# VistelV3.net
KiCad netlist of a schematic drawn in EAGLE
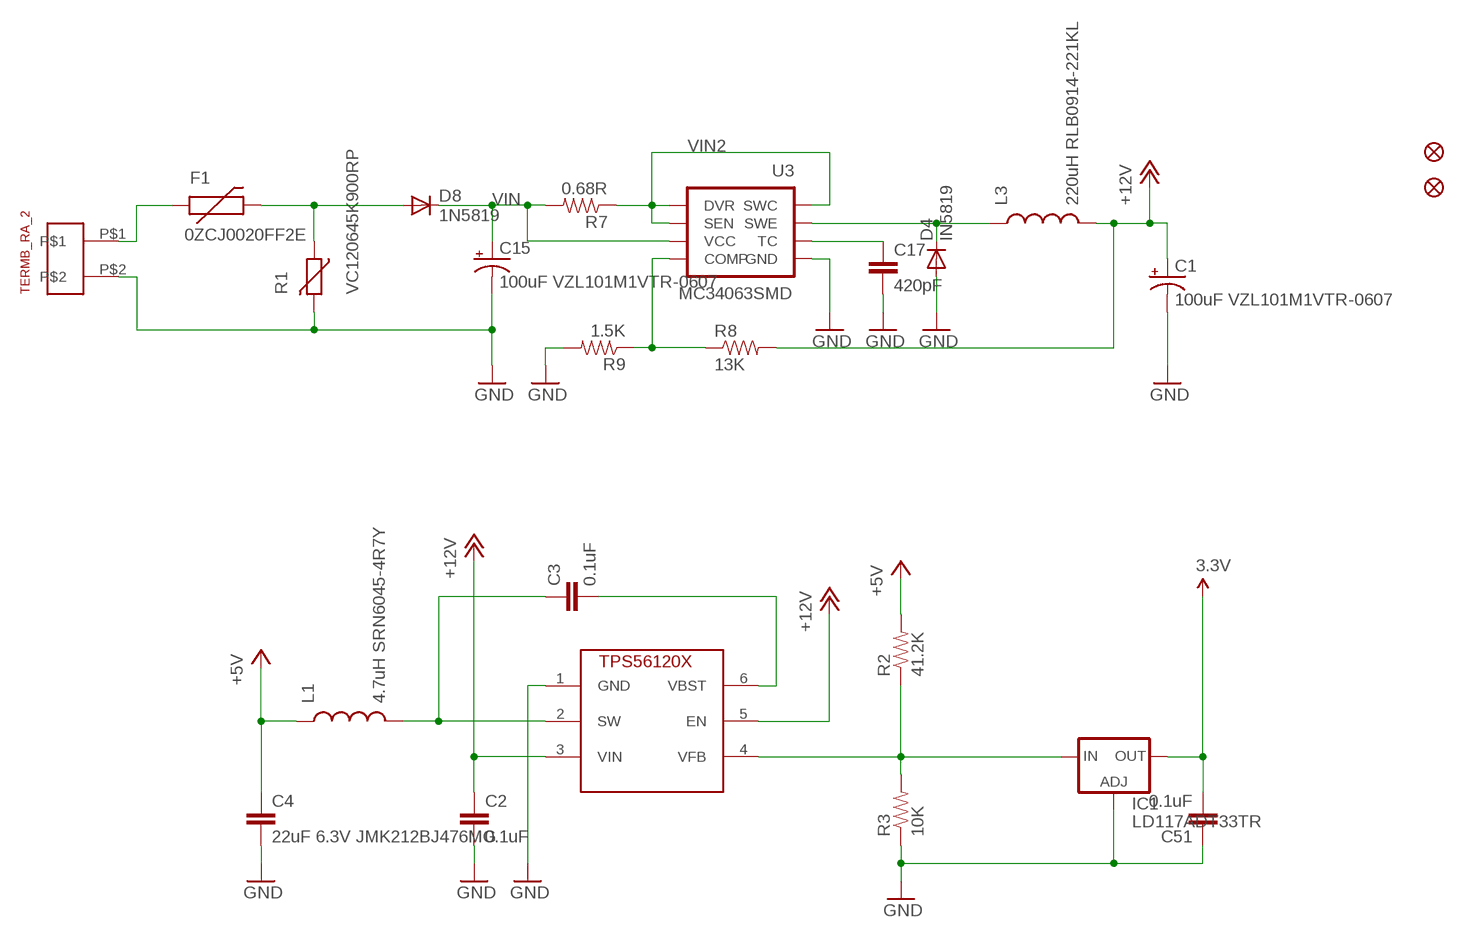
[diagram p0: schematic, sheet 1]
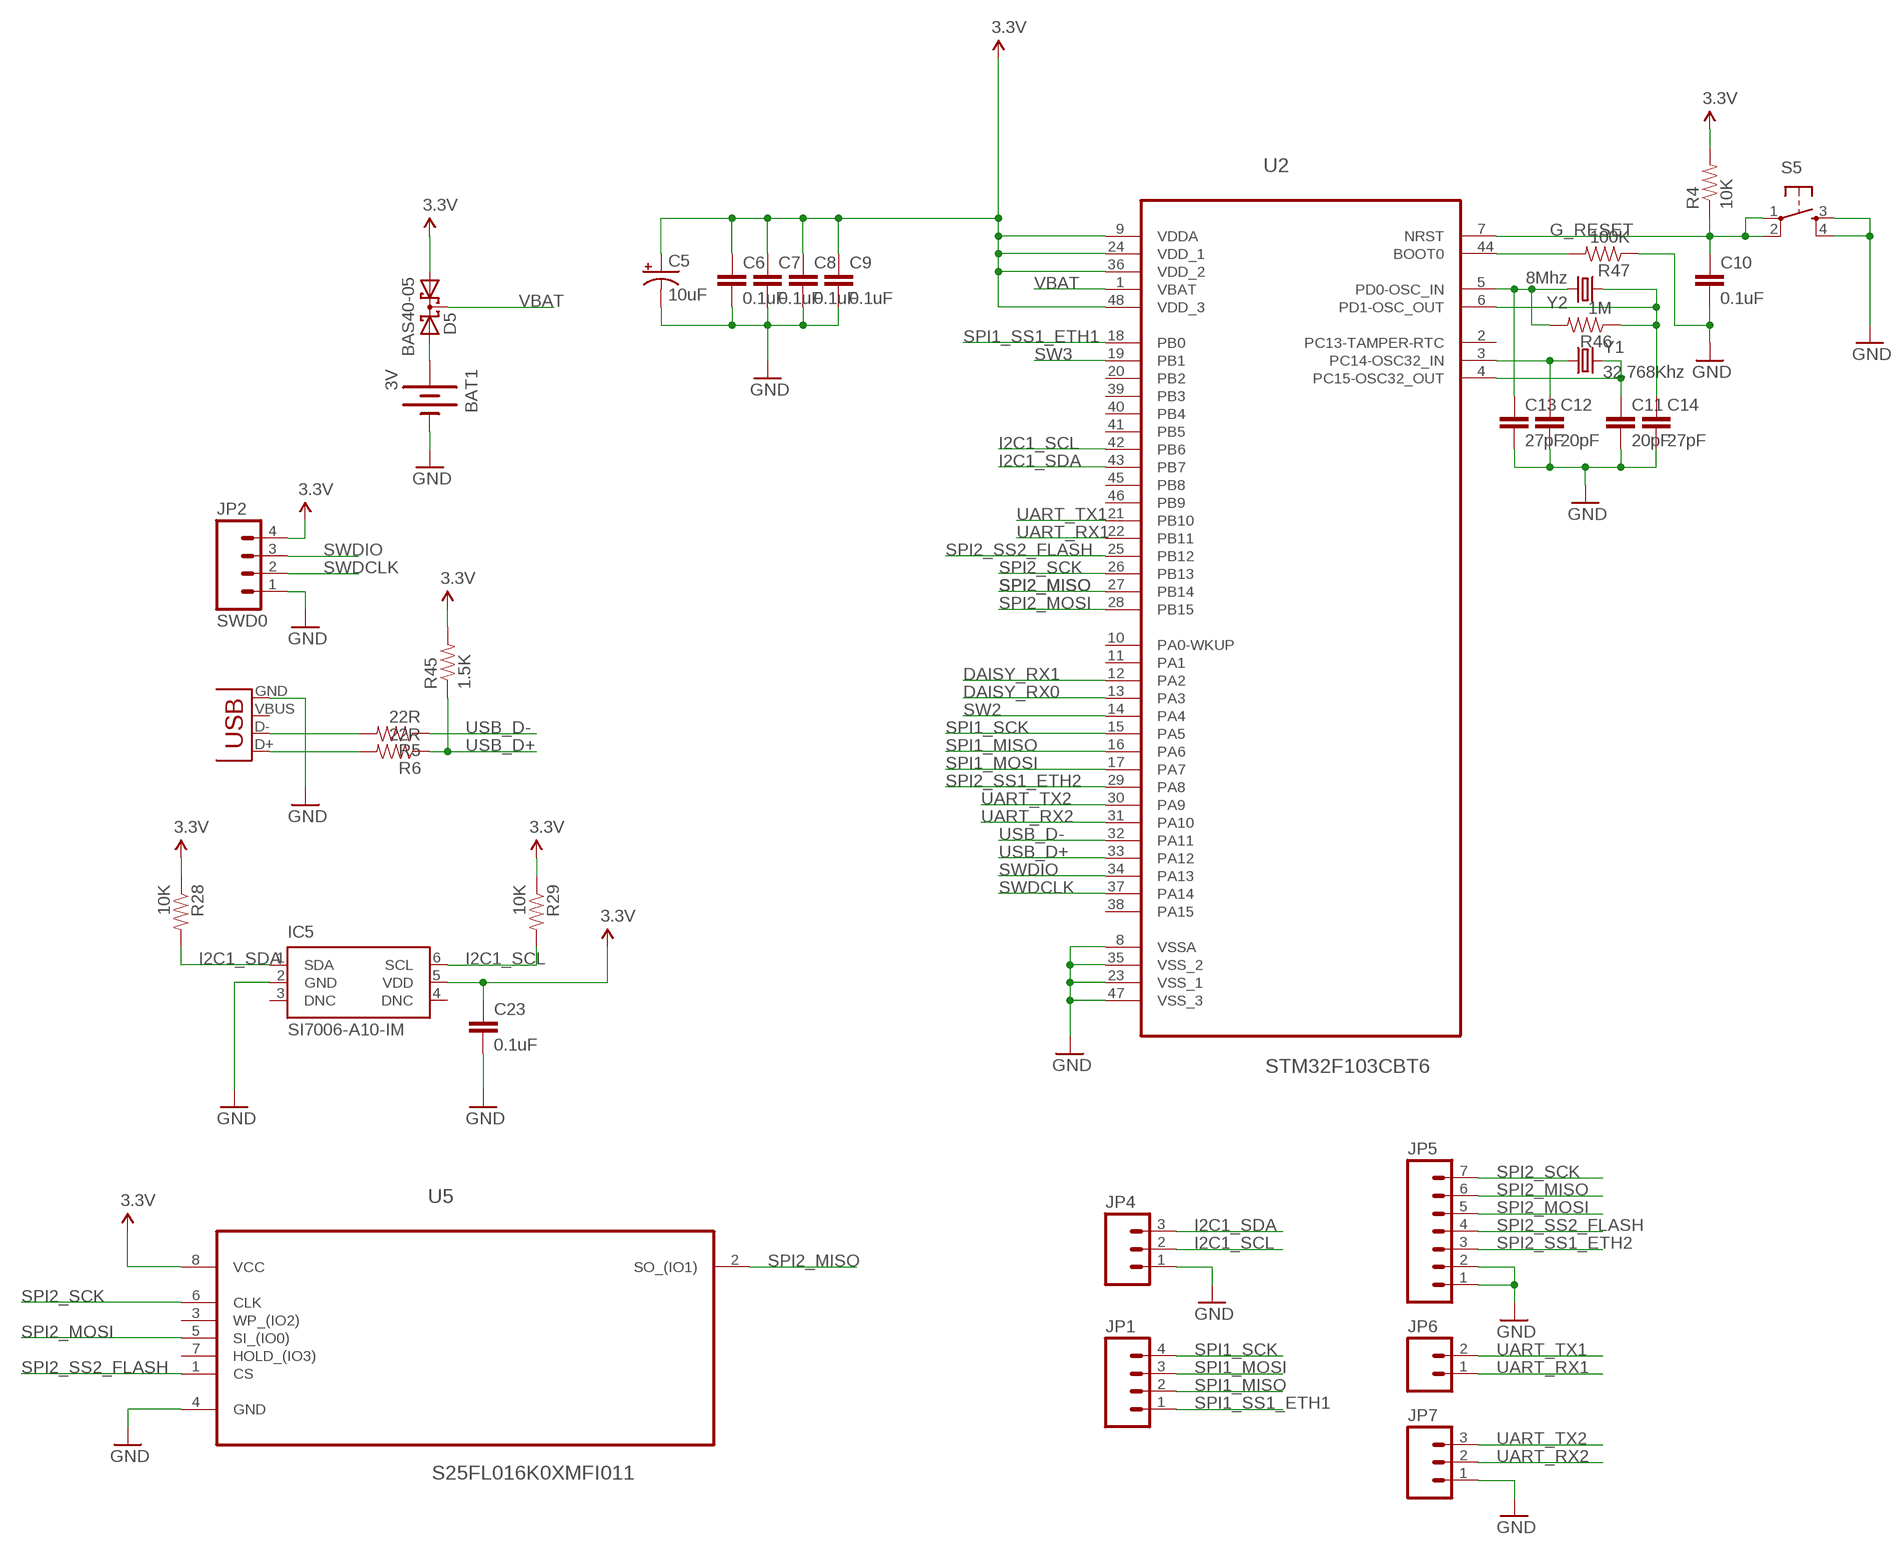
[diagram p1: schematic, sheet 2]
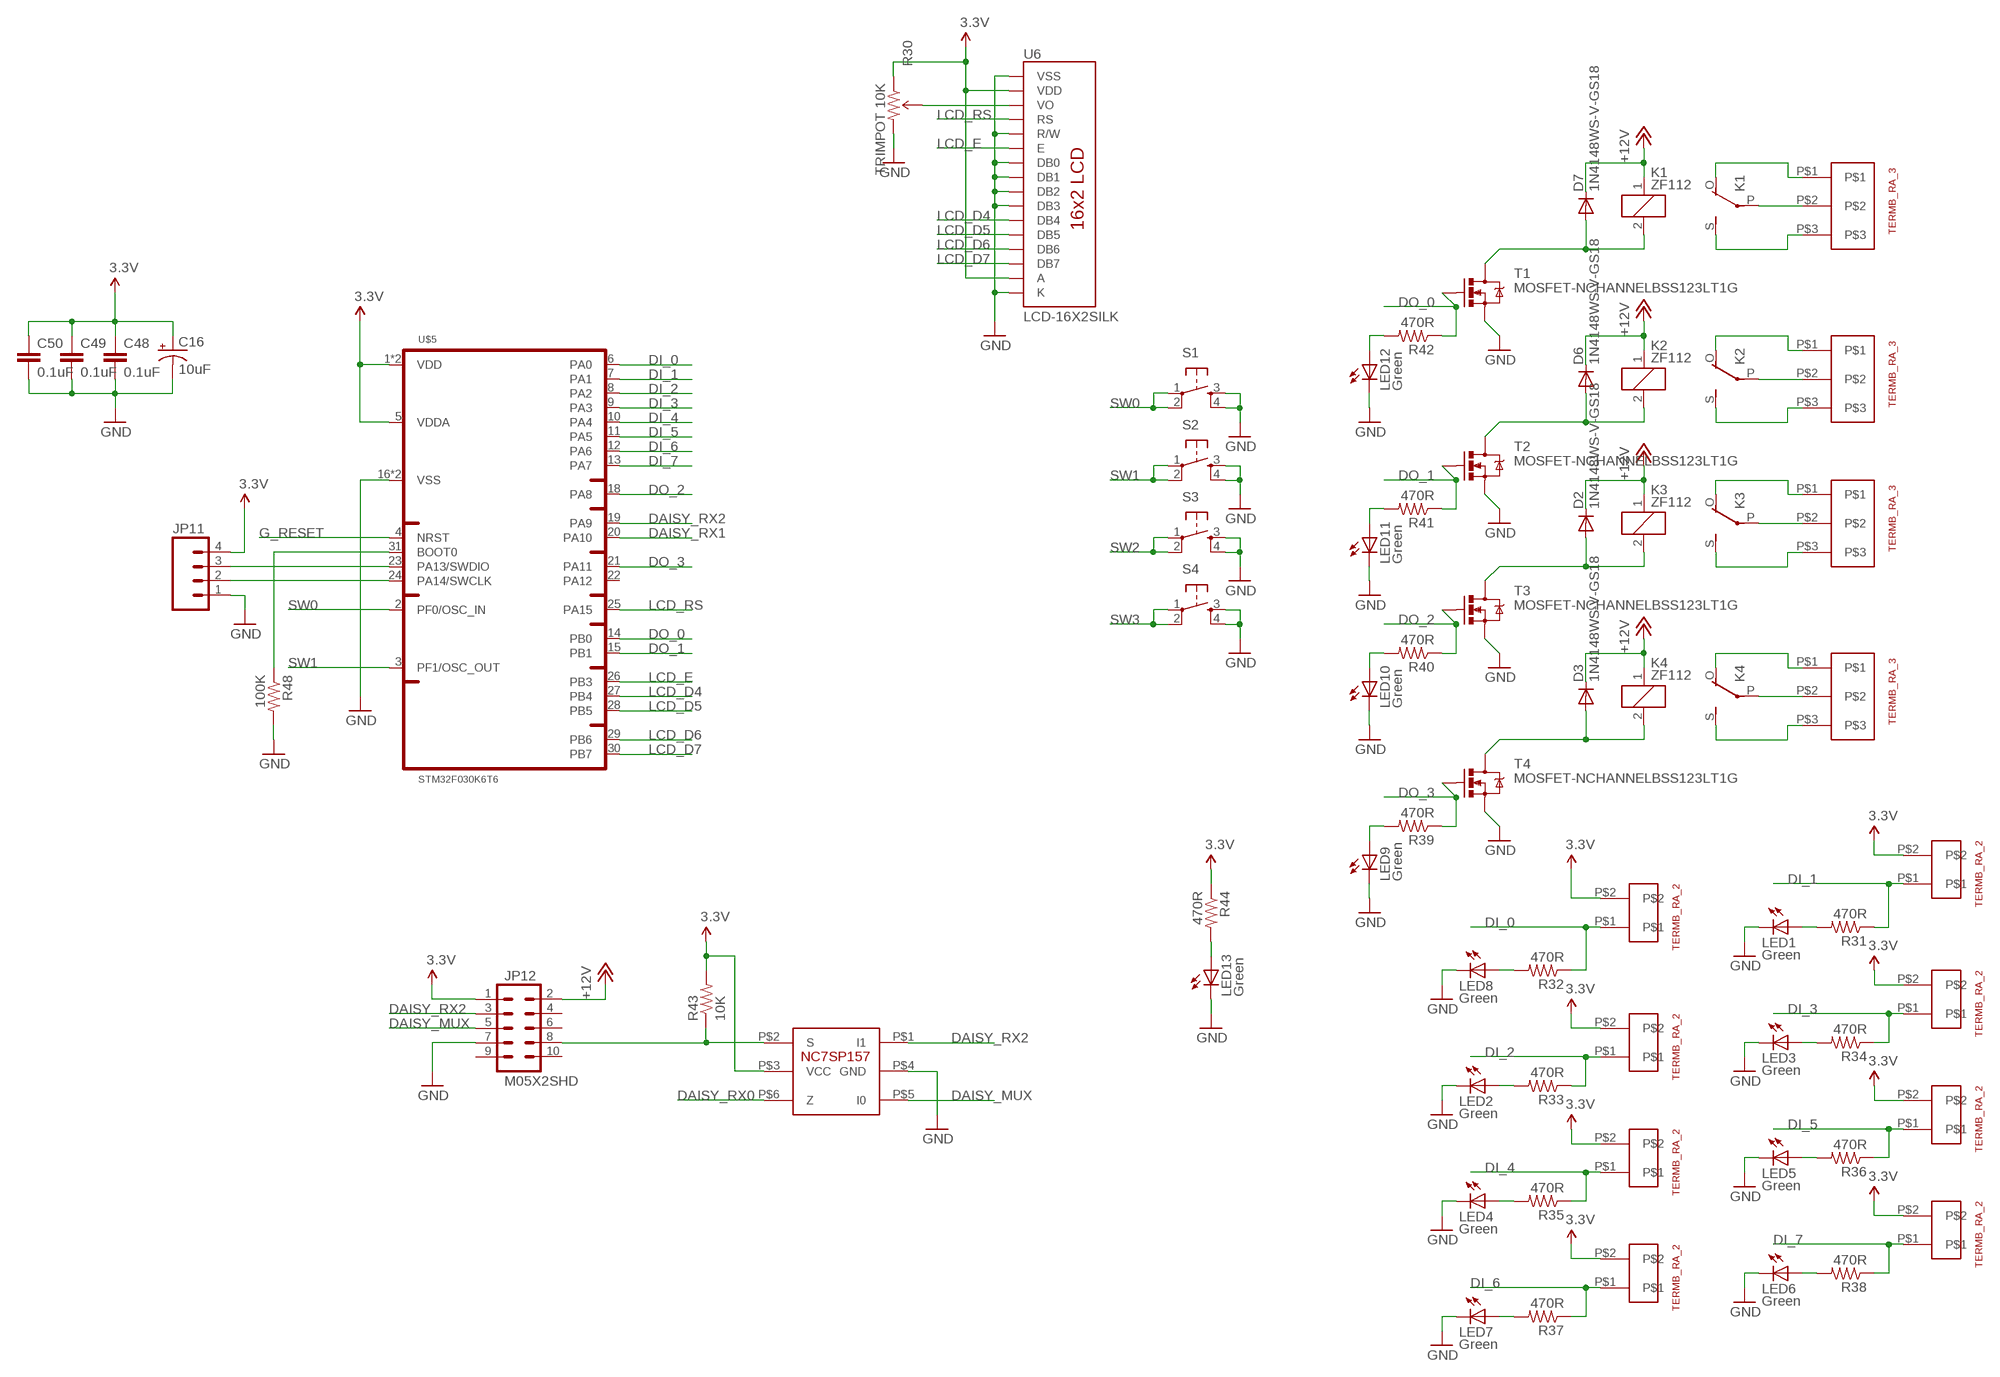
[diagram p2: schematic, sheet 3]
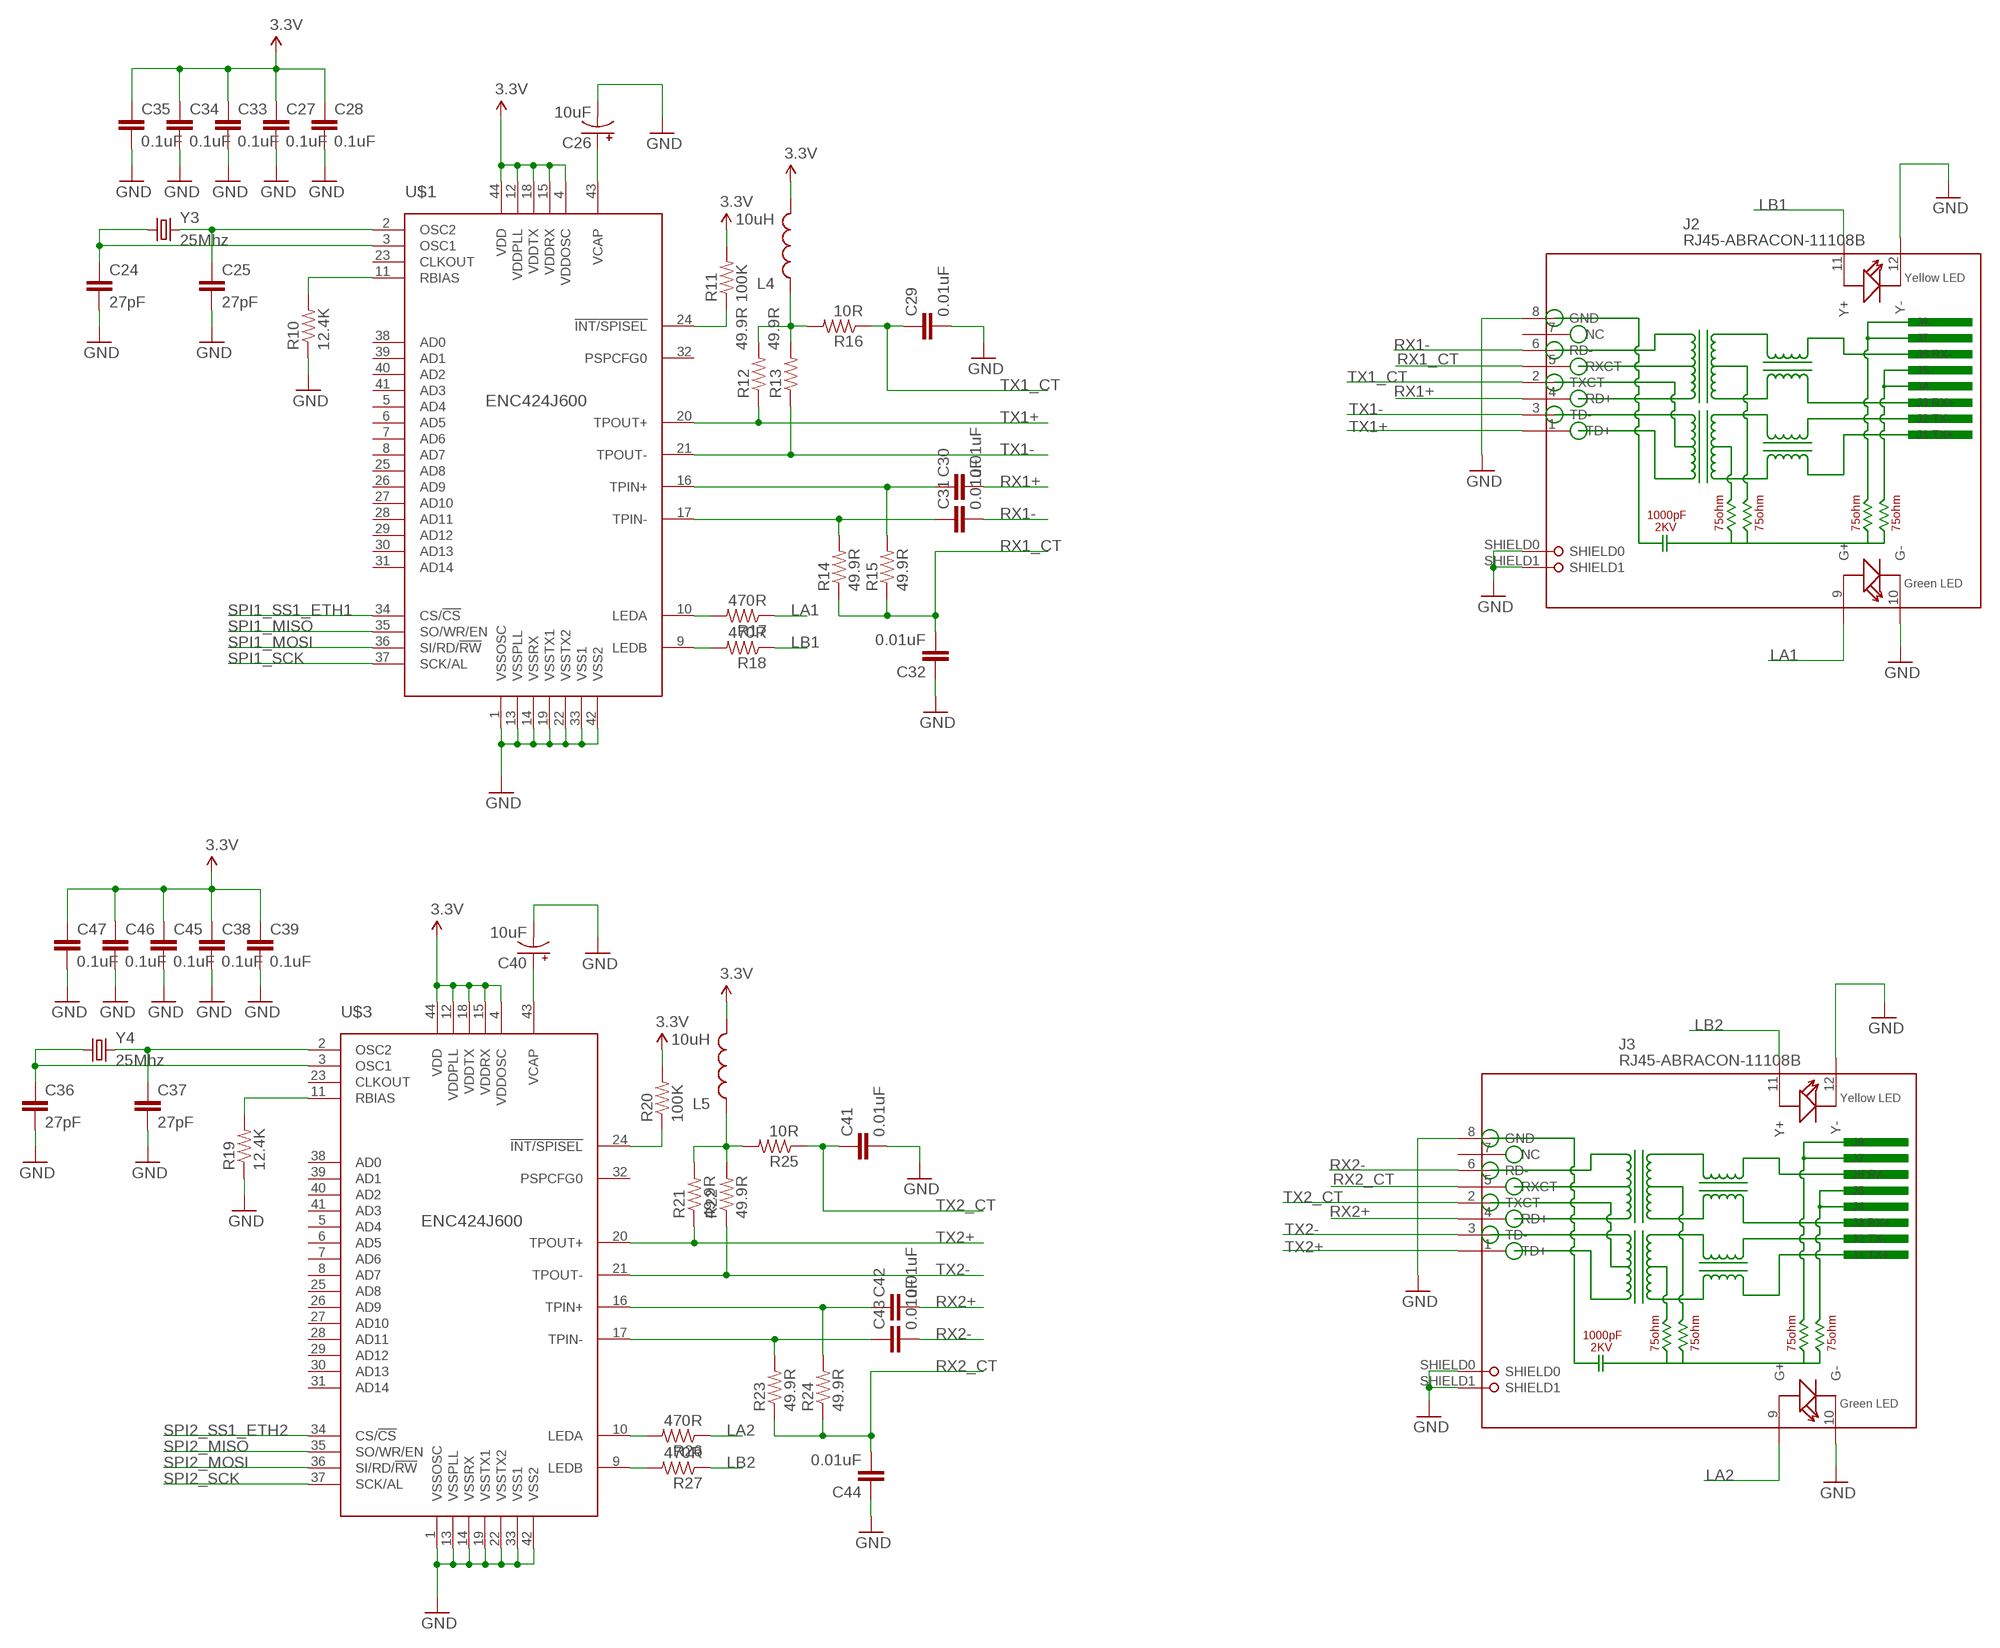
[diagram p3: schematic, sheet 4]
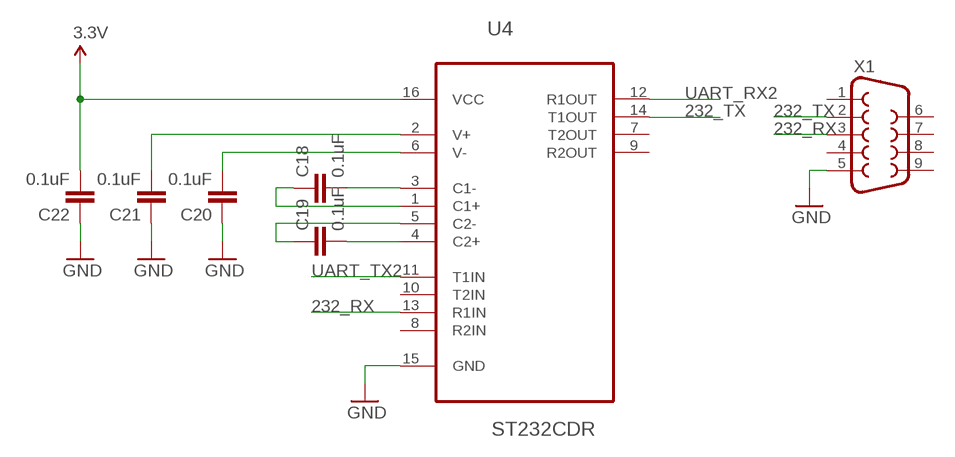
[diagram p4: schematic, sheet 5]

(export (version "E")
  (design (tool "Eeschema 10.0.6"))
  (components
    (comp (ref "C24")
      (value "27pF")
      (footprint "eagle-import:0805")
      (libsource (lib "eagle-import") (part "CAP0805"))
    )
    (comp (ref "C25")
      (value "27pF")
      (footprint "eagle-import:0805")
      (libsource (lib "eagle-import") (part "CAP0805"))
    )
    (comp (ref "C26")
      (value "10uF")
      (footprint "eagle-import:EIA3528-KIT")
      (libsource (lib "eagle-import") (part "CAP_POL3528-KIT"))
    )
    (comp (ref "C27")
      (value "0.1uF")
      (footprint "eagle-import:0805")
      (libsource (lib "eagle-import") (part "CAP0805"))
    )
    (comp (ref "C28")
      (value "0.1uF")
      (footprint "eagle-import:0805")
      (libsource (lib "eagle-import") (part "CAP0805"))
    )
    (comp (ref "C29")
      (value "0.01uF")
      (footprint "eagle-import:0805")
      (libsource (lib "eagle-import") (part "CAP0805"))
    )
    (comp (ref "C30")
      (value "0.01uF")
      (footprint "eagle-import:0805")
      (libsource (lib "eagle-import") (part "CAP0805"))
    )
    (comp (ref "C31")
      (value "0.01uF")
      (footprint "eagle-import:0805")
      (libsource (lib "eagle-import") (part "CAP0805"))
    )
    (comp (ref "C32")
      (value "0.01uF")
      (footprint "eagle-import:0805")
      (libsource (lib "eagle-import") (part "CAP0805"))
    )
    (comp (ref "C33")
      (value "0.1uF")
      (footprint "eagle-import:0805")
      (libsource (lib "eagle-import") (part "CAP0805"))
    )
    (comp (ref "C34")
      (value "0.1uF")
      (footprint "eagle-import:0805")
      (libsource (lib "eagle-import") (part "CAP0805"))
    )
    (comp (ref "C35")
      (value "0.1uF")
      (footprint "eagle-import:0805")
      (libsource (lib "eagle-import") (part "CAP0805"))
    )
    (comp (ref "C36")
      (value "27pF")
      (footprint "eagle-import:0805")
      (libsource (lib "eagle-import") (part "CAP0805"))
    )
    (comp (ref "C37")
      (value "27pF")
      (footprint "eagle-import:0805")
      (libsource (lib "eagle-import") (part "CAP0805"))
    )
    (comp (ref "C38")
      (value "0.1uF")
      (footprint "eagle-import:0805")
      (libsource (lib "eagle-import") (part "CAP0805"))
    )
    (comp (ref "C39")
      (value "0.1uF")
      (footprint "eagle-import:0805")
      (libsource (lib "eagle-import") (part "CAP0805"))
    )
    (comp (ref "C40")
      (value "10uF")
      (footprint "eagle-import:EIA3528-KIT")
      (libsource (lib "eagle-import") (part "CAP_POL3528-KIT"))
    )
    (comp (ref "C41")
      (value "0.01uF")
      (footprint "eagle-import:0805")
      (libsource (lib "eagle-import") (part "CAP0805"))
    )
    (comp (ref "C42")
      (value "0.01uF")
      (footprint "eagle-import:0805")
      (libsource (lib "eagle-import") (part "CAP0805"))
    )
    (comp (ref "C43")
      (value "0.01uF")
      (footprint "eagle-import:0805")
      (libsource (lib "eagle-import") (part "CAP0805"))
    )
    (comp (ref "C44")
      (value "0.01uF")
      (footprint "eagle-import:0805")
      (libsource (lib "eagle-import") (part "CAP0805"))
    )
    (comp (ref "C45")
      (value "0.1uF")
      (footprint "eagle-import:0805")
      (libsource (lib "eagle-import") (part "CAP0805"))
    )
    (comp (ref "C46")
      (value "0.1uF")
      (footprint "eagle-import:0805")
      (libsource (lib "eagle-import") (part "CAP0805"))
    )
    (comp (ref "C47")
      (value "0.1uF")
      (footprint "eagle-import:0805")
      (libsource (lib "eagle-import") (part "CAP0805"))
    )
    (comp (ref "J2")
      (value "RJ45-ABRACON-11108B")
      (footprint "eagle-import:RJ45-ABRACON-111008B")
      (libsource (lib "eagle-import") (part "RJ45-ABRACON-11108B"))
    )
    (comp (ref "J3")
      (value "RJ45-ABRACON-11108B")
      (footprint "eagle-import:RJ45-ABRACON-111008B")
      (libsource (lib "eagle-import") (part "RJ45-ABRACON-11108B"))
    )
    (comp (ref "L4")
      (value "10uH")
      (footprint "eagle-import:0805")
      (libsource (lib "eagle-import") (part "INDUCTOR0805"))
    )
    (comp (ref "L5")
      (value "10uH")
      (footprint "eagle-import:0805")
      (libsource (lib "eagle-import") (part "INDUCTOR0805"))
    )
    (comp (ref "R10")
      (value "12.4K")
      (footprint "eagle-import:0805")
      (libsource (lib "eagle-import") (part "SparkFun-Resistors_RESISTOR0805-RES"))
    )
    (comp (ref "R11")
      (value "100K")
      (footprint "eagle-import:0805")
      (libsource (lib "eagle-import") (part "SparkFun-Resistors_RESISTOR0805-RES"))
    )
    (comp (ref "R12")
      (value "49.9R")
      (footprint "eagle-import:0805")
      (libsource (lib "eagle-import") (part "SparkFun-Resistors_RESISTOR0805-RES"))
    )
    (comp (ref "R13")
      (value "49.9R")
      (footprint "eagle-import:0805")
      (libsource (lib "eagle-import") (part "SparkFun-Resistors_RESISTOR0805-RES"))
    )
    (comp (ref "R14")
      (value "49.9R")
      (footprint "eagle-import:0805")
      (libsource (lib "eagle-import") (part "SparkFun-Resistors_RESISTOR0805-RES"))
    )
    (comp (ref "R15")
      (value "49.9R")
      (footprint "eagle-import:0805")
      (libsource (lib "eagle-import") (part "SparkFun-Resistors_RESISTOR0805-RES"))
    )
    (comp (ref "R16")
      (value "10R")
      (footprint "eagle-import:0805")
      (libsource (lib "eagle-import") (part "SparkFun-Resistors_RESISTOR0805-RES"))
    )
    (comp (ref "R17")
      (value "470R")
      (footprint "eagle-import:0805")
      (libsource (lib "eagle-import") (part "SparkFun-Resistors_RESISTOR0805-RES"))
    )
    (comp (ref "R18")
      (value "470R")
      (footprint "eagle-import:0805")
      (libsource (lib "eagle-import") (part "SparkFun-Resistors_RESISTOR0805-RES"))
    )
    (comp (ref "R19")
      (value "12.4K")
      (footprint "eagle-import:0805")
      (libsource (lib "eagle-import") (part "SparkFun-Resistors_RESISTOR0805-RES"))
    )
    (comp (ref "R20")
      (value "100K")
      (footprint "eagle-import:0805")
      (libsource (lib "eagle-import") (part "SparkFun-Resistors_RESISTOR0805-RES"))
    )
    (comp (ref "R21")
      (value "49.9R")
      (footprint "eagle-import:0805")
      (libsource (lib "eagle-import") (part "SparkFun-Resistors_RESISTOR0805-RES"))
    )
    (comp (ref "R22")
      (value "49.9R")
      (footprint "eagle-import:0805")
      (libsource (lib "eagle-import") (part "SparkFun-Resistors_RESISTOR0805-RES"))
    )
    (comp (ref "R23")
      (value "49.9R")
      (footprint "eagle-import:0805")
      (libsource (lib "eagle-import") (part "SparkFun-Resistors_RESISTOR0805-RES"))
    )
    (comp (ref "R24")
      (value "49.9R")
      (footprint "eagle-import:0805")
      (libsource (lib "eagle-import") (part "SparkFun-Resistors_RESISTOR0805-RES"))
    )
    (comp (ref "R25")
      (value "10R")
      (footprint "eagle-import:0805")
      (libsource (lib "eagle-import") (part "SparkFun-Resistors_RESISTOR0805-RES"))
    )
    (comp (ref "R26")
      (value "470R")
      (footprint "eagle-import:0805")
      (libsource (lib "eagle-import") (part "SparkFun-Resistors_RESISTOR0805-RES"))
    )
    (comp (ref "R27")
      (value "470R")
      (footprint "eagle-import:0805")
      (libsource (lib "eagle-import") (part "SparkFun-Resistors_RESISTOR0805-RES"))
    )
    (comp (ref "U$1")
      (value "ENC424J600")
      (footprint "eagle-import:TQFP-44")
      (libsource (lib "eagle-import") (part "ENC424J600"))
    )
    (comp (ref "U$3")
      (value "ENC424J600")
      (footprint "eagle-import:TQFP-44")
      (libsource (lib "eagle-import") (part "ENC424J600"))
    )
    (comp (ref "Y3")
      (value "25Mhz")
      (footprint "eagle-import:CRYSTAL-SMD-10.5X4.8-2PIN")
      (libsource (lib "eagle-import") (part "CRYSTAL10.5X4.8"))
    )
    (comp (ref "Y4")
      (value "25Mhz")
      (footprint "eagle-import:CRYSTAL-SMD-10.5X4.8-2PIN")
      (libsource (lib "eagle-import") (part "CRYSTAL10.5X4.8"))
    )
    (comp (ref "C16")
      (value "10uF")
      (footprint "eagle-import:EIA3216")
      (libsource (lib "eagle-import") (part "10UF-TANT"))
    )
    (comp (ref "C48")
      (value "0.1uF")
      (footprint "eagle-import:0805")
      (libsource (lib "eagle-import") (part "CAP0805"))
    )
    (comp (ref "C49")
      (value "0.1uF")
      (footprint "eagle-import:0805")
      (libsource (lib "eagle-import") (part "CAP0805"))
    )
    (comp (ref "C50")
      (value "0.1uF")
      (footprint "eagle-import:0805")
      (libsource (lib "eagle-import") (part "CAP0805"))
    )
    (comp (ref "D2")
      (value "1N4148WS-V-GS18")
      (footprint "eagle-import:SMA-DIODE_ALT")
      (libsource (lib "eagle-import") (part "DIODESMA-ALT"))
    )
    (comp (ref "D3")
      (value "1N4148WS-V-GS18")
      (footprint "eagle-import:SMA-DIODE_ALT")
      (libsource (lib "eagle-import") (part "DIODESMA-ALT"))
    )
    (comp (ref "D6")
      (value "1N4148WS-V-GS18")
      (footprint "eagle-import:SMA-DIODE_ALT")
      (libsource (lib "eagle-import") (part "DIODESMA-ALT"))
    )
    (comp (ref "D7")
      (value "1N4148WS-V-GS18")
      (footprint "eagle-import:SMA-DIODE_ALT")
      (libsource (lib "eagle-import") (part "DIODESMA-ALT"))
    )
    (comp (ref "JP11")
      (value "M04PTH")
      (footprint "eagle-import:1X04")
      (libsource (lib "eagle-import") (part "M04PTH"))
    )
    (comp (ref "JP12")
      (value "M05X2SHD")
      (footprint "eagle-import:2X5-SHROUDED")
      (libsource (lib "eagle-import") (part "M05X2SHD"))
    )
    (comp (ref "K1")
      (value "ZF112")
      (footprint "eagle-import:ZF112")
      (libsource (lib "eagle-import") (part "ZF112"))
    )
    (comp (ref "K2")
      (value "ZF112")
      (footprint "eagle-import:ZF112")
      (libsource (lib "eagle-import") (part "ZF112"))
    )
    (comp (ref "K3")
      (value "ZF112")
      (footprint "eagle-import:ZF112")
      (libsource (lib "eagle-import") (part "ZF112"))
    )
    (comp (ref "K4")
      (value "ZF112")
      (footprint "eagle-import:ZF112")
      (libsource (lib "eagle-import") (part "ZF112"))
    )
    (comp (ref "LED1")
      (value "Green")
      (footprint "eagle-import:LED-1206")
      (libsource (lib "eagle-import") (part "LED1206"))
    )
    (comp (ref "LED2")
      (value "Green")
      (footprint "eagle-import:LED-1206")
      (libsource (lib "eagle-import") (part "LED1206"))
    )
    (comp (ref "LED3")
      (value "Green")
      (footprint "eagle-import:LED-1206")
      (libsource (lib "eagle-import") (part "LED1206"))
    )
    (comp (ref "LED4")
      (value "Green")
      (footprint "eagle-import:LED-1206")
      (libsource (lib "eagle-import") (part "LED1206"))
    )
    (comp (ref "LED5")
      (value "Green")
      (footprint "eagle-import:LED-1206")
      (libsource (lib "eagle-import") (part "LED1206"))
    )
    (comp (ref "LED6")
      (value "Green")
      (footprint "eagle-import:LED-1206")
      (libsource (lib "eagle-import") (part "LED1206"))
    )
    (comp (ref "LED7")
      (value "Green")
      (footprint "eagle-import:LED-1206")
      (libsource (lib "eagle-import") (part "LED1206"))
    )
    (comp (ref "LED8")
      (value "Green")
      (footprint "eagle-import:LED-1206")
      (libsource (lib "eagle-import") (part "LED1206"))
    )
    (comp (ref "LED9")
      (value "Green")
      (footprint "eagle-import:LED-1206")
      (libsource (lib "eagle-import") (part "LED1206"))
    )
    (comp (ref "LED10")
      (value "Green")
      (footprint "eagle-import:LED-1206")
      (libsource (lib "eagle-import") (part "LED1206"))
    )
    (comp (ref "LED11")
      (value "Green")
      (footprint "eagle-import:LED-1206")
      (libsource (lib "eagle-import") (part "LED1206"))
    )
    (comp (ref "LED12")
      (value "Green")
      (footprint "eagle-import:LED-1206")
      (libsource (lib "eagle-import") (part "LED1206"))
    )
    (comp (ref "LED13")
      (value "Green")
      (footprint "eagle-import:LED-1206")
      (libsource (lib "eagle-import") (part "LED1206"))
    )
    (comp (ref "R30")
      (value "TRIMPOT 10K")
      (footprint "eagle-import:TRIM_POT_PTH")
      (libsource (lib "eagle-import") (part "TRIMPOTPTH"))
    )
    (comp (ref "R31")
      (value "470R")
      (footprint "eagle-import:0805")
      (libsource (lib "eagle-import") (part "RESISTOR0805-RES"))
    )
    (comp (ref "R32")
      (value "470R")
      (footprint "eagle-import:0805")
      (libsource (lib "eagle-import") (part "RESISTOR0805-RES"))
    )
    (comp (ref "R33")
      (value "470R")
      (footprint "eagle-import:0805")
      (libsource (lib "eagle-import") (part "RESISTOR0805-RES"))
    )
    (comp (ref "R34")
      (value "470R")
      (footprint "eagle-import:0805")
      (libsource (lib "eagle-import") (part "RESISTOR0805-RES"))
    )
    (comp (ref "R35")
      (value "470R")
      (footprint "eagle-import:0805")
      (libsource (lib "eagle-import") (part "RESISTOR0805-RES"))
    )
    (comp (ref "R36")
      (value "470R")
      (footprint "eagle-import:0805")
      (libsource (lib "eagle-import") (part "RESISTOR0805-RES"))
    )
    (comp (ref "R37")
      (value "470R")
      (footprint "eagle-import:0805")
      (libsource (lib "eagle-import") (part "RESISTOR0805-RES"))
    )
    (comp (ref "R38")
      (value "470R")
      (footprint "eagle-import:0805")
      (libsource (lib "eagle-import") (part "RESISTOR0805-RES"))
    )
    (comp (ref "R39")
      (value "470R")
      (footprint "eagle-import:0805")
      (libsource (lib "eagle-import") (part "RESISTOR0805-RES"))
    )
    (comp (ref "R40")
      (value "470R")
      (footprint "eagle-import:0805")
      (libsource (lib "eagle-import") (part "RESISTOR0805-RES"))
    )
    (comp (ref "R41")
      (value "470R")
      (footprint "eagle-import:0805")
      (libsource (lib "eagle-import") (part "RESISTOR0805-RES"))
    )
    (comp (ref "R42")
      (value "470R")
      (footprint "eagle-import:0805")
      (libsource (lib "eagle-import") (part "RESISTOR0805-RES"))
    )
    (comp (ref "R43")
      (value "10K")
      (footprint "eagle-import:0805")
      (libsource (lib "eagle-import") (part "RESISTOR0805-RES"))
    )
    (comp (ref "R44")
      (value "470R")
      (footprint "eagle-import:0805")
      (libsource (lib "eagle-import") (part "RESISTOR0805-RES"))
    )
    (comp (ref "R48")
      (value "100K")
      (footprint "eagle-import:0805")
      (libsource (lib "eagle-import") (part "RESISTOR0805-RES"))
    )
    (comp (ref "S1")
      (value "TAC_SWITCHPTH")
      (footprint "eagle-import:TACTILE-PTH")
      (libsource (lib "eagle-import") (part "TAC_SWITCHPTH"))
    )
    (comp (ref "S2")
      (value "TAC_SWITCHPTH")
      (footprint "eagle-import:TACTILE-PTH")
      (libsource (lib "eagle-import") (part "TAC_SWITCHPTH"))
    )
    (comp (ref "S3")
      (value "TAC_SWITCHPTH")
      (footprint "eagle-import:TACTILE-PTH")
      (libsource (lib "eagle-import") (part "TAC_SWITCHPTH"))
    )
    (comp (ref "S4")
      (value "TAC_SWITCHPTH")
      (footprint "eagle-import:TACTILE-PTH")
      (libsource (lib "eagle-import") (part "TAC_SWITCHPTH"))
    )
    (comp (ref "T1")
      (value "MOSFET-NCHANNELBSS123LT1G")
      (footprint "eagle-import:SOT23")
      (libsource (lib "eagle-import") (part "MOSFET-NCHANNELBSS123LT1G"))
    )
    (comp (ref "T2")
      (value "MOSFET-NCHANNELBSS123LT1G")
      (footprint "eagle-import:SOT23")
      (libsource (lib "eagle-import") (part "MOSFET-NCHANNELBSS123LT1G"))
    )
    (comp (ref "T3")
      (value "MOSFET-NCHANNELBSS123LT1G")
      (footprint "eagle-import:SOT23")
      (libsource (lib "eagle-import") (part "MOSFET-NCHANNELBSS123LT1G"))
    )
    (comp (ref "T4")
      (value "MOSFET-NCHANNELBSS123LT1G")
      (footprint "eagle-import:SOT23")
      (libsource (lib "eagle-import") (part "MOSFET-NCHANNELBSS123LT1G"))
    )
    (comp (ref "U$4")
      (value "NC7SP157")
      (footprint "eagle-import:SC70-6")
      (libsource (lib "eagle-import") (part "NC7SP157"))
    )
    (comp (ref "U$5")
      (value "STM32F030K6T6")
      (footprint "eagle-import:LQFP32-7X7")
      (libsource (lib "eagle-import") (part "STM32F030K6T6"))
    )
    (comp (ref "U$6")
      (value "1X02_TERMB_RA")
      (footprint "eagle-import:1X02_TERMB_RA")
      (libsource (lib "eagle-import") (part "1X02_TERMB_RA"))
    )
    (comp (ref "U$7")
      (value "1X02_TERMB_RA")
      (footprint "eagle-import:1X02_TERMB_RA")
      (libsource (lib "eagle-import") (part "1X02_TERMB_RA"))
    )
    (comp (ref "U$8")
      (value "1X02_TERMB_RA")
      (footprint "eagle-import:1X02_TERMB_RA")
      (libsource (lib "eagle-import") (part "1X02_TERMB_RA"))
    )
    (comp (ref "U$9")
      (value "1X02_TERMB_RA")
      (footprint "eagle-import:1X02_TERMB_RA")
      (libsource (lib "eagle-import") (part "1X02_TERMB_RA"))
    )
    (comp (ref "U$10")
      (value "1X02_TERMB_RA")
      (footprint "eagle-import:1X02_TERMB_RA")
      (libsource (lib "eagle-import") (part "1X02_TERMB_RA"))
    )
    (comp (ref "U$11")
      (value "1X02_TERMB_RA")
      (footprint "eagle-import:1X02_TERMB_RA")
      (libsource (lib "eagle-import") (part "1X02_TERMB_RA"))
    )
    (comp (ref "U$12")
      (value "1X02_TERMB_RA")
      (footprint "eagle-import:1X02_TERMB_RA")
      (libsource (lib "eagle-import") (part "1X02_TERMB_RA"))
    )
    (comp (ref "U$13")
      (value "1X02_TERMB_RA")
      (footprint "eagle-import:1X02_TERMB_RA")
      (libsource (lib "eagle-import") (part "1X02_TERMB_RA"))
    )
    (comp (ref "U$14")
      (value "1X03_TERMB_RA")
      (footprint "eagle-import:1X03_TERMB_RA")
      (libsource (lib "eagle-import") (part "1X03_TERMB_RA"))
    )
    (comp (ref "U$15")
      (value "1X03_TERMB_RA")
      (footprint "eagle-import:1X03_TERMB_RA")
      (libsource (lib "eagle-import") (part "1X03_TERMB_RA"))
    )
    (comp (ref "U$16")
      (value "1X03_TERMB_RA")
      (footprint "eagle-import:1X03_TERMB_RA")
      (libsource (lib "eagle-import") (part "1X03_TERMB_RA"))
    )
    (comp (ref "U$17")
      (value "1X03_TERMB_RA")
      (footprint "eagle-import:1X03_TERMB_RA")
      (libsource (lib "eagle-import") (part "1X03_TERMB_RA"))
    )
    (comp (ref "U6")
      (value "LCD-16X2SILK")
      (footprint "eagle-import:LCD-16X2")
      (libsource (lib "eagle-import") (part "LCD-16X2SILK"))
    )
    (comp (ref "C18")
      (value "0.1uF")
      (footprint "eagle-import:0805")
      (libsource (lib "eagle-import") (part "SparkFun-Passives_CAP0805"))
    )
    (comp (ref "C19")
      (value "0.1uF")
      (footprint "eagle-import:0805")
      (libsource (lib "eagle-import") (part "SparkFun-Passives_CAP0805"))
    )
    (comp (ref "C20")
      (value "0.1uF")
      (footprint "eagle-import:0805")
      (libsource (lib "eagle-import") (part "SparkFun-Passives_CAP0805"))
    )
    (comp (ref "C21")
      (value "0.1uF")
      (footprint "eagle-import:0805")
      (libsource (lib "eagle-import") (part "SparkFun-Passives_CAP0805"))
    )
    (comp (ref "C22")
      (value "0.1uF")
      (footprint "eagle-import:0805")
      (libsource (lib "eagle-import") (part "SparkFun-Passives_CAP0805"))
    )
    (comp (ref "U4")
      (value "ST232CDR")
      (footprint "eagle-import:SOIC127P600X175-16N")
      (libsource (lib "eagle-import") (part "ST232CDR"))
    )
    (comp (ref "X1")
      (value "DB9FEMALE")
      (footprint "eagle-import:DB9")
      (libsource (lib "eagle-import") (part "DB9FEMALE"))
    )
    (comp (ref "BAT1")
      (value "3V")
      (footprint "eagle-import:BATTCOM_20MM_PTH")
      (libsource (lib "eagle-import") (part "BATTERY20PTH"))
    )
    (comp (ref "C5")
      (value "10uF")
      (footprint "eagle-import:EIA3216")
      (libsource (lib "eagle-import") (part "10UF-TANT"))
    )
    (comp (ref "C6")
      (value "0.1uF")
      (footprint "eagle-import:0805")
      (libsource (lib "eagle-import") (part "CAP0805"))
    )
    (comp (ref "C7")
      (value "0.1uF")
      (footprint "eagle-import:0805")
      (libsource (lib "eagle-import") (part "CAP0805"))
    )
    (comp (ref "C8")
      (value "0.1uF")
      (footprint "eagle-import:0805")
      (libsource (lib "eagle-import") (part "CAP0805"))
    )
    (comp (ref "C9")
      (value "0.1uF")
      (footprint "eagle-import:0805")
      (libsource (lib "eagle-import") (part "CAP0805"))
    )
    (comp (ref "C10")
      (value "0.1uF")
      (footprint "eagle-import:0805")
      (libsource (lib "eagle-import") (part "CAP0805"))
    )
    (comp (ref "C11")
      (value "20pF")
      (footprint "eagle-import:0805")
      (libsource (lib "eagle-import") (part "CAP0805"))
    )
    (comp (ref "C12")
      (value "20pF")
      (footprint "eagle-import:0805")
      (libsource (lib "eagle-import") (part "CAP0805"))
    )
    (comp (ref "C13")
      (value "27pF")
      (footprint "eagle-import:0805")
      (libsource (lib "eagle-import") (part "CAP0805"))
    )
    (comp (ref "C14")
      (value "27pF")
      (footprint "eagle-import:0805")
      (libsource (lib "eagle-import") (part "CAP0805"))
    )
    (comp (ref "C23")
      (value "0.1uF")
      (footprint "eagle-import:0805")
      (libsource (lib "eagle-import") (part "CAP0805"))
    )
    (comp (ref "D5")
      (value "BAS40-05")
      (footprint "eagle-import:SOT23")
      (libsource (lib "eagle-import") (part "BAS40-05"))
    )
    (comp (ref "IC5")
      (value "SI7006-A10-IM")
      (footprint "eagle-import:DFN6-3X3")
      (fields (field (name "MF") "Silicon Labs") (field (name "MPN") "Si7006-A10-IM"))
      (libsource (lib "eagle-import") (part "SI7006-A10-IM"))
    )
    (comp (ref "JP1")
      (value "M04PTH")
      (footprint "eagle-import:1X04")
      (libsource (lib "eagle-import") (part "M04PTH"))
    )
    (comp (ref "JP2")
      (value "SWD0")
      (footprint "eagle-import:1X04")
      (libsource (lib "eagle-import") (part "M04PTH"))
    )
    (comp (ref "JP3")
      (value "USB-B")
      (footprint "eagle-import:USB-B-PTH")
      (libsource (lib "eagle-import") (part "USBPTH"))
    )
    (comp (ref "JP4")
      (value "M03PTH")
      (footprint "eagle-import:1X03")
      (libsource (lib "eagle-import") (part "M03PTH"))
    )
    (comp (ref "JP5")
      (value "M07")
      (footprint "eagle-import:1X07")
      (libsource (lib "eagle-import") (part "M07"))
    )
    (comp (ref "JP6")
      (value "M02PTH")
      (footprint "eagle-import:1X02")
      (libsource (lib "eagle-import") (part "M02PTH"))
    )
    (comp (ref "JP7")
      (value "M03PTH")
      (footprint "eagle-import:1X03")
      (libsource (lib "eagle-import") (part "M03PTH"))
    )
    (comp (ref "R4")
      (value "10K")
      (footprint "eagle-import:0805")
      (libsource (lib "eagle-import") (part "SparkFun-Resistors_RESISTOR0805-RES"))
    )
    (comp (ref "R5")
      (value "22R")
      (footprint "eagle-import:0805")
      (libsource (lib "eagle-import") (part "SparkFun-Resistors_RESISTOR0805-RES"))
    )
    (comp (ref "R6")
      (value "22R")
      (footprint "eagle-import:0805")
      (libsource (lib "eagle-import") (part "SparkFun-Resistors_RESISTOR0805-RES"))
    )
    (comp (ref "R28")
      (value "10K")
      (footprint "eagle-import:0805")
      (libsource (lib "eagle-import") (part "SparkFun-Resistors_RESISTOR0805-RES"))
    )
    (comp (ref "R29")
      (value "10K")
      (footprint "eagle-import:0805")
      (libsource (lib "eagle-import") (part "SparkFun-Resistors_RESISTOR0805-RES"))
    )
    (comp (ref "R45")
      (value "1.5K")
      (footprint "eagle-import:0805")
      (libsource (lib "eagle-import") (part "SparkFun-Resistors_RESISTOR0805-RES"))
    )
    (comp (ref "R46")
      (value "1M")
      (footprint "eagle-import:0805")
      (libsource (lib "eagle-import") (part "SparkFun-Resistors_RESISTOR0805-RES"))
    )
    (comp (ref "R47")
      (value "100K")
      (footprint "eagle-import:0805")
      (libsource (lib "eagle-import") (part "SparkFun-Resistors_RESISTOR0805-RES"))
    )
    (comp (ref "S5")
      (value "TAC_SWITCHPTH")
      (footprint "eagle-import:TACTILE-PTH")
      (libsource (lib "eagle-import") (part "TAC_SWITCHPTH"))
    )
    (comp (ref "U2")
      (value "STM32F103CBT6")
      (footprint "eagle-import:QFP50P900X900X160-48N")
      (libsource (lib "eagle-import") (part "STM32F103CBT6"))
    )
    (comp (ref "U5")
      (value "S25FL016K0XMFI011")
      (footprint "eagle-import:SOIC127P800X215-8N")
      (libsource (lib "eagle-import") (part "S25FL016K0XMFI011"))
    )
    (comp (ref "Y1")
      (value "32.768Khz")
      (footprint "eagle-import:MC-306")
      (fields (field (name "MPN") "MC-306 60.0KHZ  100PPM ,12.5PF"))
      (libsource (lib "eagle-import") (part "MC-306"))
    )
    (comp (ref "Y2")
      (value "8Mhz")
      (footprint "eagle-import:HC49US")
      (libsource (lib "eagle-import") (part "CRYSTALHC49US"))
    )
    (comp (ref "C1")
      (value "100uF VZL101M1VTR-0607")
      (footprint "eagle-import:PANASONIC_D")
      (libsource (lib "eagle-import") (part "CAP_POLD"))
    )
    (comp (ref "C2")
      (value "0.1uF")
      (footprint "eagle-import:0805")
      (libsource (lib "eagle-import") (part "SparkFun-Passives_CAP0805"))
    )
    (comp (ref "C3")
      (value "0.1uF")
      (footprint "eagle-import:0805")
      (libsource (lib "eagle-import") (part "SparkFun-Passives_CAP0805"))
    )
    (comp (ref "C4")
      (value "22uF 6.3V JMK212BJ476MG")
      (footprint "eagle-import:0805")
      (libsource (lib "eagle-import") (part "SparkFun-Passives_CAP0805"))
    )
    (comp (ref "C15")
      (value "100uF VZL101M1VTR-0607")
      (footprint "eagle-import:PANASONIC_D")
      (libsource (lib "eagle-import") (part "CAP_POLD"))
    )
    (comp (ref "C17")
      (value "420pF")
      (footprint "eagle-import:0805")
      (libsource (lib "eagle-import") (part "SparkFun-Passives_CAP0805"))
    )
    (comp (ref "C51")
      (value "0.1uF")
      (footprint "eagle-import:0805")
      (libsource (lib "eagle-import") (part "SparkFun-Passives_CAP0805"))
    )
    (comp (ref "D4")
      (value "IN5819")
      (footprint "eagle-import:SMA-DIODE")
      (libsource (lib "eagle-import") (part "DIODESMA"))
    )
    (comp (ref "D8")
      (value "1N5819")
      (footprint "eagle-import:SMB-DIODE")
      (libsource (lib "eagle-import") (part "DIODESMB"))
    )
    (comp (ref "F1")
      (value "0ZCJ0020FF2E")
      (footprint "eagle-import:PTC-1206")
      (libsource (lib "eagle-import") (part "PTCSMD"))
    )
    (comp (ref "FID1")
      (value "FIDUCIAL1.5X3")
      (footprint "eagle-import:FIDUCIAL-1.5X3")
      (libsource (lib "eagle-import") (part "FIDUCIAL1.5X3"))
    )
    (comp (ref "FID2")
      (value "FIDUCIAL1.5X3")
      (footprint "eagle-import:FIDUCIAL-1.5X3")
      (libsource (lib "eagle-import") (part "FIDUCIAL1.5X3"))
    )
    (comp (ref "IC1")
      (value "LD117ADT33TR")
      (footprint "eagle-import:DPACK")
      (libsource (lib "eagle-import") (part "LD117A?DT33TR"))
    )
    (comp (ref "L1")
      (value "4.7uH SRN6045-4R7Y")
      (footprint "eagle-import:0805")
      (libsource (lib "eagle-import") (part "INDUCTOR0805"))
    )
    (comp (ref "L3")
      (value "220uH RLB0914-221KL")
      (footprint "eagle-import:RLB914-IND")
      (libsource (lib "eagle-import") (part "INDUCTORRADIAL5MM"))
    )
    (comp (ref "R1")
      (value "VC120645K900RP")
      (footprint "eagle-import:CT_CN1206")
      (libsource (lib "eagle-import") (part "VARISTORCN1206"))
    )
    (comp (ref "R2")
      (value "41.2K")
      (footprint "eagle-import:0805")
      (libsource (lib "eagle-import") (part "RESISTOR0805-RES"))
    )
    (comp (ref "R3")
      (value "10K")
      (footprint "eagle-import:0805")
      (libsource (lib "eagle-import") (part "RESISTOR0805-RES"))
    )
    (comp (ref "R7")
      (value "0.68R")
      (footprint "eagle-import:0805")
      (libsource (lib "eagle-import") (part "RESISTOR0805-RES"))
    )
    (comp (ref "R8")
      (value "13K")
      (footprint "eagle-import:0805")
      (libsource (lib "eagle-import") (part "RESISTOR0805-RES"))
    )
    (comp (ref "R9")
      (value "1.5K")
      (footprint "eagle-import:0805")
      (libsource (lib "eagle-import") (part "RESISTOR0805-RES"))
    )
    (comp (ref "U$2")
      (value "1X02_TERMB_RA")
      (footprint "eagle-import:1X02_TERMB_RA")
      (libsource (lib "eagle-import") (part "1X02_TERMB_RA"))
    )
    (comp (ref "U$18")
      (value "TPS56120X")
      (footprint "eagle-import:TSOT23-6_DDC")
      (libsource (lib "eagle-import") (part "TPS56120X"))
    )
    (comp (ref "U3")
      (value "MC34063SMD")
      (footprint "eagle-import:SO08")
      (libsource (lib "eagle-import") (part "MC34063SMD"))
    )
  )
  (nets
    (net (code "1") (name "+5V") (class "Default")
      (node (ref "C4") (pin "1") (pinfunction "1_1") (pintype "passive"))
      (node (ref "L1") (pin "1") (pinfunction "1_1") (pintype "passive"))
      (node (ref "R2") (pin "2") (pinfunction "2_2") (pintype "passive"))
    )
    (net (code "2") (name "+12V") (class "Default")
      (node (ref "C1") (pin "+") (pinfunction "+_+") (pintype "passive"))
      (node (ref "C2") (pin "1") (pinfunction "1_1") (pintype "passive"))
      (node (ref "D2") (pin "C") (pinfunction "C_C") (pintype "passive"))
      (node (ref "D3") (pin "C") (pinfunction "C_C") (pintype "passive"))
      (node (ref "D6") (pin "C") (pinfunction "C_C") (pintype "passive"))
      (node (ref "D7") (pin "C") (pinfunction "C_C") (pintype "passive"))
      (node (ref "JP12") (pin "2") (pinfunction "2_2") (pintype "passive"))
      (node (ref "K1") (pin "1") (pinfunction "1_1") (pintype "passive"))
      (node (ref "K2") (pin "1") (pinfunction "1_1") (pintype "passive"))
      (node (ref "K3") (pin "1") (pinfunction "1_1") (pintype "passive"))
      (node (ref "K4") (pin "1") (pinfunction "1_1") (pintype "passive"))
      (node (ref "L3") (pin "P$2") (pinfunction "2_P$2") (pintype "passive"))
      (node (ref "R8") (pin "2") (pinfunction "2_2") (pintype "passive"))
      (node (ref "U$18") (pin "3") (pinfunction "VIN_3") (pintype "bidirectional"))
      (node (ref "U$18") (pin "5") (pinfunction "EN_5") (pintype "bidirectional"))
    )
    (net (code "3") (name "3.3V") (class "Default")
      (node (ref "C16") (pin "A") (pinfunction "+_A") (pintype "passive"))
      (node (ref "C22") (pin "2") (pinfunction "2_2") (pintype "passive"))
      (node (ref "C23") (pin "1") (pinfunction "1_1") (pintype "passive"))
      (node (ref "C27") (pin "1") (pinfunction "1_1") (pintype "passive"))
      (node (ref "C28") (pin "1") (pinfunction "1_1") (pintype "passive"))
      (node (ref "C33") (pin "1") (pinfunction "1_1") (pintype "passive"))
      (node (ref "C34") (pin "1") (pinfunction "1_1") (pintype "passive"))
      (node (ref "C35") (pin "1") (pinfunction "1_1") (pintype "passive"))
      (node (ref "C38") (pin "1") (pinfunction "1_1") (pintype "passive"))
      (node (ref "C39") (pin "1") (pinfunction "1_1") (pintype "passive"))
      (node (ref "C45") (pin "1") (pinfunction "1_1") (pintype "passive"))
      (node (ref "C46") (pin "1") (pinfunction "1_1") (pintype "passive"))
      (node (ref "C47") (pin "1") (pinfunction "1_1") (pintype "passive"))
      (node (ref "C48") (pin "1") (pinfunction "1_1") (pintype "passive"))
      (node (ref "C49") (pin "1") (pinfunction "1_1") (pintype "passive"))
      (node (ref "C5") (pin "A") (pinfunction "+_A") (pintype "passive"))
      (node (ref "C50") (pin "1") (pinfunction "1_1") (pintype "passive"))
      (node (ref "C51") (pin "2") (pinfunction "2_2") (pintype "passive"))
      (node (ref "C6") (pin "1") (pinfunction "1_1") (pintype "passive"))
      (node (ref "C7") (pin "1") (pinfunction "1_1") (pintype "passive"))
      (node (ref "C8") (pin "1") (pinfunction "1_1") (pintype "passive"))
      (node (ref "C9") (pin "1") (pinfunction "1_1") (pintype "passive"))
      (node (ref "D5") (pin "1") (pinfunction "A1_1") (pintype "passive"))
      (node (ref "IC1") (pin "4") (pinfunction "OUT_4") (pintype "passive"))
      (node (ref "IC5") (pin "5") (pinfunction "VDD_5") (pintype "power_in"))
      (node (ref "JP11") (pin "4") (pinfunction "4_4") (pintype "passive"))
      (node (ref "JP12") (pin "1") (pinfunction "1_1") (pintype "passive"))
      (node (ref "JP2") (pin "4") (pinfunction "4_4") (pintype "passive"))
      (node (ref "L4") (pin "2") (pinfunction "2_2") (pintype "passive"))
      (node (ref "L5") (pin "2") (pinfunction "2_2") (pintype "passive"))
      (node (ref "R11") (pin "2") (pinfunction "2_2") (pintype "passive"))
      (node (ref "R20") (pin "2") (pinfunction "2_2") (pintype "passive"))
      (node (ref "R28") (pin "1") (pinfunction "1_1") (pintype "passive"))
      (node (ref "R29") (pin "1") (pinfunction "1_1") (pintype "passive"))
      (node (ref "R30") (pin "1") (pinfunction "CCW_1") (pintype "passive"))
      (node (ref "R4") (pin "2") (pinfunction "2_2") (pintype "passive"))
      (node (ref "R43") (pin "2") (pinfunction "2_2") (pintype "passive"))
      (node (ref "R44") (pin "1") (pinfunction "1_1") (pintype "passive"))
      (node (ref "R45") (pin "2") (pinfunction "2_2") (pintype "passive"))
      (node (ref "U$1") (pin "12") (pinfunction "VDDPLL_12") (pintype "bidirectional"))
      (node (ref "U$1") (pin "15") (pinfunction "VDDRX_15") (pintype "bidirectional"))
      (node (ref "U$1") (pin "18") (pinfunction "VDDTX_18") (pintype "bidirectional"))
      (node (ref "U$1") (pin "4") (pinfunction "VDDOSC_4") (pintype "bidirectional"))
      (node (ref "U$1") (pin "44") (pinfunction "VDD_44") (pintype "bidirectional"))
      (node (ref "U$10") (pin "P$2") (pinfunction "P$2_P$2") (pintype "bidirectional"))
      (node (ref "U$11") (pin "P$2") (pinfunction "P$2_P$2") (pintype "bidirectional"))
      (node (ref "U$12") (pin "P$2") (pinfunction "P$2_P$2") (pintype "bidirectional"))
      (node (ref "U$13") (pin "P$2") (pinfunction "P$2_P$2") (pintype "bidirectional"))
      (node (ref "U$3") (pin "12") (pinfunction "VDDPLL_12") (pintype "bidirectional"))
      (node (ref "U$3") (pin "15") (pinfunction "VDDRX_15") (pintype "bidirectional"))
      (node (ref "U$3") (pin "18") (pinfunction "VDDTX_18") (pintype "bidirectional"))
      (node (ref "U$3") (pin "4") (pinfunction "VDDOSC_4") (pintype "bidirectional"))
      (node (ref "U$3") (pin "44") (pinfunction "VDD_44") (pintype "bidirectional"))
      (node (ref "U$4") (pin "P$3") (pinfunction "VCC_P$3") (pintype "bidirectional"))
      (node (ref "U$5") (pin "1") (pinfunction "VDD_1") (pintype "bidirectional"))
      (node (ref "U$5") (pin "17") (pinfunction "VDD_17") (pintype "bidirectional"))
      (node (ref "U$5") (pin "5") (pinfunction "VDDA_5") (pintype "bidirectional"))
      (node (ref "U$6") (pin "P$2") (pinfunction "P$2_P$2") (pintype "bidirectional"))
      (node (ref "U$7") (pin "P$2") (pinfunction "P$2_P$2") (pintype "bidirectional"))
      (node (ref "U$8") (pin "P$2") (pinfunction "P$2_P$2") (pintype "bidirectional"))
      (node (ref "U$9") (pin "P$2") (pinfunction "P$2_P$2") (pintype "bidirectional"))
      (node (ref "U2") (pin "24") (pinfunction "VDD_1_24") (pintype "bidirectional"))
      (node (ref "U2") (pin "36") (pinfunction "VDD_2_36") (pintype "power_in"))
      (node (ref "U2") (pin "48") (pinfunction "VDD_3_48") (pintype "power_in"))
      (node (ref "U2") (pin "9") (pinfunction "VDDA_9") (pintype "power_in"))
      (node (ref "U4") (pin "16") (pinfunction "VCC_16") (pintype "power_in"))
      (node (ref "U5") (pin "8") (pinfunction "VCC_8") (pintype "power_in"))
      (node (ref "U6") (pin "15") (pinfunction "A_15") (pintype "power_in"))
      (node (ref "U6") (pin "2") (pinfunction "VDD_2") (pintype "power_in"))
    )
    (net (code "4") (name "232_RX") (class "Default")
      (node (ref "U4") (pin "13") (pinfunction "R1IN_13") (pintype "input"))
      (node (ref "X1") (pin "3") (pinfunction "3_3") (pintype "passive"))
    )
    (net (code "5") (name "232_TX") (class "Default")
      (node (ref "U4") (pin "14") (pinfunction "T1OUT_14") (pintype "output"))
      (node (ref "X1") (pin "2") (pinfunction "2_2") (pintype "passive"))
    )
    (net (code "6") (name "DAISY_MUX") (class "Default")
      (node (ref "JP12") (pin "5") (pinfunction "5_5") (pintype "passive"))
      (node (ref "U$4") (pin "P$5") (pinfunction "I0_P$5") (pintype "bidirectional"))
    )
    (net (code "7") (name "DAISY_RX0") (class "Default")
      (node (ref "U$4") (pin "P$6") (pinfunction "Z_P$6") (pintype "bidirectional"))
      (node (ref "U2") (pin "13") (pinfunction "PA3_13") (pintype "bidirectional"))
    )
    (net (code "8") (name "DAISY_RX1") (class "Default")
      (node (ref "U$5") (pin "20") (pinfunction "PA10_20") (pintype "bidirectional"))
      (node (ref "U2") (pin "12") (pinfunction "PA2_12") (pintype "bidirectional"))
    )
    (net (code "9") (name "DAISY_RX2") (class "Default")
      (node (ref "JP12") (pin "3") (pinfunction "3_3") (pintype "passive"))
      (node (ref "U$4") (pin "P$1") (pinfunction "I1_P$1") (pintype "bidirectional"))
      (node (ref "U$5") (pin "19") (pinfunction "PA9_19") (pintype "bidirectional"))
    )
    (net (code "10") (name "DI_0") (class "Default")
      (node (ref "R32") (pin "1") (pinfunction "1_1") (pintype "passive"))
      (node (ref "U$5") (pin "6") (pinfunction "PA0_6") (pintype "bidirectional"))
      (node (ref "U$6") (pin "P$1") (pinfunction "P$1_P$1") (pintype "bidirectional"))
    )
    (net (code "11") (name "DI_1") (class "Default")
      (node (ref "R31") (pin "1") (pinfunction "1_1") (pintype "passive"))
      (node (ref "U$5") (pin "7") (pinfunction "PA1_7") (pintype "bidirectional"))
      (node (ref "U$7") (pin "P$1") (pinfunction "P$1_P$1") (pintype "bidirectional"))
    )
    (net (code "12") (name "DI_2") (class "Default")
      (node (ref "R33") (pin "1") (pinfunction "1_1") (pintype "passive"))
      (node (ref "U$13") (pin "P$1") (pinfunction "P$1_P$1") (pintype "bidirectional"))
      (node (ref "U$5") (pin "8") (pinfunction "PA2_8") (pintype "bidirectional"))
    )
    (net (code "13") (name "DI_3") (class "Default")
      (node (ref "R34") (pin "1") (pinfunction "1_1") (pintype "passive"))
      (node (ref "U$5") (pin "9") (pinfunction "PA3_9") (pintype "bidirectional"))
      (node (ref "U$8") (pin "P$1") (pinfunction "P$1_P$1") (pintype "bidirectional"))
    )
    (net (code "14") (name "DI_4") (class "Default")
      (node (ref "R35") (pin "1") (pinfunction "1_1") (pintype "passive"))
      (node (ref "U$12") (pin "P$1") (pinfunction "P$1_P$1") (pintype "bidirectional"))
      (node (ref "U$5") (pin "10") (pinfunction "PA4_10") (pintype "bidirectional"))
    )
    (net (code "15") (name "DI_5") (class "Default")
      (node (ref "R36") (pin "1") (pinfunction "1_1") (pintype "passive"))
      (node (ref "U$5") (pin "11") (pinfunction "PA5_11") (pintype "bidirectional"))
      (node (ref "U$9") (pin "P$1") (pinfunction "P$1_P$1") (pintype "bidirectional"))
    )
    (net (code "16") (name "DI_6") (class "Default")
      (node (ref "R37") (pin "1") (pinfunction "1_1") (pintype "passive"))
      (node (ref "U$11") (pin "P$1") (pinfunction "P$1_P$1") (pintype "bidirectional"))
      (node (ref "U$5") (pin "12") (pinfunction "PA6_12") (pintype "bidirectional"))
    )
    (net (code "17") (name "DI_7") (class "Default")
      (node (ref "R38") (pin "1") (pinfunction "1_1") (pintype "passive"))
      (node (ref "U$10") (pin "P$1") (pinfunction "P$1_P$1") (pintype "bidirectional"))
      (node (ref "U$5") (pin "13") (pinfunction "PA7_13") (pintype "bidirectional"))
    )
    (net (code "18") (name "DO_0") (class "Default")
      (node (ref "R42") (pin "1") (pinfunction "1_1") (pintype "passive"))
      (node (ref "T1") (pin "1") (pinfunction "G_1") (pintype "passive"))
      (node (ref "U$5") (pin "14") (pinfunction "PB0_14") (pintype "bidirectional"))
    )
    (net (code "19") (name "DO_1") (class "Default")
      (node (ref "R41") (pin "1") (pinfunction "1_1") (pintype "passive"))
      (node (ref "T2") (pin "1") (pinfunction "G_1") (pintype "passive"))
      (node (ref "U$5") (pin "15") (pinfunction "PB1_15") (pintype "bidirectional"))
    )
    (net (code "20") (name "DO_2") (class "Default")
      (node (ref "R40") (pin "1") (pinfunction "1_1") (pintype "passive"))
      (node (ref "T3") (pin "1") (pinfunction "G_1") (pintype "passive"))
      (node (ref "U$5") (pin "18") (pinfunction "PA8_18") (pintype "bidirectional"))
    )
    (net (code "21") (name "DO_3") (class "Default")
      (node (ref "R39") (pin "1") (pinfunction "1_1") (pintype "passive"))
      (node (ref "T4") (pin "1") (pinfunction "G_1") (pintype "passive"))
      (node (ref "U$5") (pin "21") (pinfunction "PA11_21") (pintype "bidirectional"))
    )
    (net (code "22") (name "GND") (class "Default")
      (node (ref "BAT1") (pin "2") (pinfunction "-_2") (pintype "power_in"))
      (node (ref "C1") (pin "-") (pinfunction "-_-") (pintype "passive"))
      (node (ref "C10") (pin "2") (pinfunction "2_2") (pintype "passive"))
      (node (ref "C11") (pin "2") (pinfunction "2_2") (pintype "passive"))
      (node (ref "C12") (pin "2") (pinfunction "2_2") (pintype "passive"))
      (node (ref "C13") (pin "2") (pinfunction "2_2") (pintype "passive"))
      (node (ref "C14") (pin "2") (pinfunction "2_2") (pintype "passive"))
      (node (ref "C15") (pin "-") (pinfunction "-_-") (pintype "passive"))
      (node (ref "C16") (pin "C") (pinfunction "-_C") (pintype "passive"))
      (node (ref "C17") (pin "2") (pinfunction "2_2") (pintype "passive"))
      (node (ref "C2") (pin "2") (pinfunction "2_2") (pintype "passive"))
      (node (ref "C20") (pin "1") (pinfunction "1_1") (pintype "passive"))
      (node (ref "C21") (pin "1") (pinfunction "1_1") (pintype "passive"))
      (node (ref "C22") (pin "1") (pinfunction "1_1") (pintype "passive"))
      (node (ref "C23") (pin "2") (pinfunction "2_2") (pintype "passive"))
      (node (ref "C24") (pin "2") (pinfunction "2_2") (pintype "passive"))
      (node (ref "C25") (pin "2") (pinfunction "2_2") (pintype "passive"))
      (node (ref "C26") (pin "C") (pinfunction "-_C") (pintype "passive"))
      (node (ref "C27") (pin "2") (pinfunction "2_2") (pintype "passive"))
      (node (ref "C28") (pin "2") (pinfunction "2_2") (pintype "passive"))
      (node (ref "C29") (pin "2") (pinfunction "2_2") (pintype "passive"))
      (node (ref "C32") (pin "1") (pinfunction "1_1") (pintype "passive"))
      (node (ref "C33") (pin "2") (pinfunction "2_2") (pintype "passive"))
      (node (ref "C34") (pin "2") (pinfunction "2_2") (pintype "passive"))
      (node (ref "C35") (pin "2") (pinfunction "2_2") (pintype "passive"))
      (node (ref "C36") (pin "2") (pinfunction "2_2") (pintype "passive"))
      (node (ref "C37") (pin "2") (pinfunction "2_2") (pintype "passive"))
      (node (ref "C38") (pin "2") (pinfunction "2_2") (pintype "passive"))
      (node (ref "C39") (pin "2") (pinfunction "2_2") (pintype "passive"))
      (node (ref "C4") (pin "2") (pinfunction "2_2") (pintype "passive"))
      (node (ref "C40") (pin "C") (pinfunction "-_C") (pintype "passive"))
      (node (ref "C41") (pin "2") (pinfunction "2_2") (pintype "passive"))
      (node (ref "C44") (pin "1") (pinfunction "1_1") (pintype "passive"))
      (node (ref "C45") (pin "2") (pinfunction "2_2") (pintype "passive"))
      (node (ref "C46") (pin "2") (pinfunction "2_2") (pintype "passive"))
      (node (ref "C47") (pin "2") (pinfunction "2_2") (pintype "passive"))
      (node (ref "C48") (pin "2") (pinfunction "2_2") (pintype "passive"))
      (node (ref "C49") (pin "2") (pinfunction "2_2") (pintype "passive"))
      (node (ref "C5") (pin "C") (pinfunction "-_C") (pintype "passive"))
      (node (ref "C50") (pin "2") (pinfunction "2_2") (pintype "passive"))
      (node (ref "C51") (pin "1") (pinfunction "1_1") (pintype "passive"))
      (node (ref "C6") (pin "2") (pinfunction "2_2") (pintype "passive"))
      (node (ref "C7") (pin "2") (pinfunction "2_2") (pintype "passive"))
      (node (ref "C8") (pin "2") (pinfunction "2_2") (pintype "passive"))
      (node (ref "C9") (pin "2") (pinfunction "2_2") (pintype "passive"))
      (node (ref "D4") (pin "A") (pinfunction "A_A") (pintype "passive"))
      (node (ref "IC1") (pin "1") (pinfunction "ADJ_1") (pintype "input"))
      (node (ref "IC5") (pin "2") (pinfunction "GND_2") (pintype "power_in"))
      (node (ref "J2") (pin "10") (pinfunction "G-_10") (pintype "bidirectional"))
      (node (ref "J2") (pin "12") (pinfunction "Y-_12") (pintype "bidirectional"))
      (node (ref "J2") (pin "8") (pinfunction "GND_8") (pintype "bidirectional"))
      (node (ref "J2") (pin "SHIELD0") (pinfunction "SHIELD0_SHIELD0") (pintype "bidirectional"))
      (node (ref "J2") (pin "SHIELD1") (pinfunction "SHIELD1_SHIELD1") (pintype "bidirectional"))
      (node (ref "J3") (pin "10") (pinfunction "G-_10") (pintype "bidirectional"))
      (node (ref "J3") (pin "12") (pinfunction "Y-_12") (pintype "bidirectional"))
      (node (ref "J3") (pin "8") (pinfunction "GND_8") (pintype "bidirectional"))
      (node (ref "J3") (pin "SHIELD0") (pinfunction "SHIELD0_SHIELD0") (pintype "bidirectional"))
      (node (ref "J3") (pin "SHIELD1") (pinfunction "SHIELD1_SHIELD1") (pintype "bidirectional"))
      (node (ref "JP11") (pin "1") (pinfunction "1_1") (pintype "passive"))
      (node (ref "JP12") (pin "7") (pinfunction "7_7") (pintype "passive"))
      (node (ref "JP2") (pin "1") (pinfunction "1_1") (pintype "passive"))
      (node (ref "JP3") (pin "GND") (pinfunction "GND_GND") (pintype "bidirectional"))
      (node (ref "JP4") (pin "1") (pinfunction "1_1") (pintype "passive"))
      (node (ref "JP5") (pin "1") (pinfunction "1_1") (pintype "passive"))
      (node (ref "JP5") (pin "2") (pinfunction "2_2") (pintype "passive"))
      (node (ref "JP7") (pin "1") (pinfunction "1_1") (pintype "passive"))
      (node (ref "LED1") (pin "C") (pinfunction "C_C") (pintype "passive"))
      (node (ref "LED10") (pin "C") (pinfunction "C_C") (pintype "passive"))
      (node (ref "LED11") (pin "C") (pinfunction "C_C") (pintype "passive"))
      (node (ref "LED12") (pin "C") (pinfunction "C_C") (pintype "passive"))
      (node (ref "LED13") (pin "C") (pinfunction "C_C") (pintype "passive"))
      (node (ref "LED2") (pin "C") (pinfunction "C_C") (pintype "passive"))
      (node (ref "LED3") (pin "C") (pinfunction "C_C") (pintype "passive"))
      (node (ref "LED4") (pin "C") (pinfunction "C_C") (pintype "passive"))
      (node (ref "LED5") (pin "C") (pinfunction "C_C") (pintype "passive"))
      (node (ref "LED6") (pin "C") (pinfunction "C_C") (pintype "passive"))
      (node (ref "LED7") (pin "C") (pinfunction "C_C") (pintype "passive"))
      (node (ref "LED8") (pin "C") (pinfunction "C_C") (pintype "passive"))
      (node (ref "LED9") (pin "C") (pinfunction "C_C") (pintype "passive"))
      (node (ref "R1") (pin "2") (pinfunction "2_2") (pintype "passive"))
      (node (ref "R10") (pin "1") (pinfunction "1_1") (pintype "passive"))
      (node (ref "R19") (pin "1") (pinfunction "1_1") (pintype "passive"))
      (node (ref "R3") (pin "1") (pinfunction "1_1") (pintype "passive"))
      (node (ref "R30") (pin "3") (pinfunction "CW_3") (pintype "passive"))
      (node (ref "R47") (pin "1") (pinfunction "1_1") (pintype "passive"))
      (node (ref "R48") (pin "2") (pinfunction "2_2") (pintype "passive"))
      (node (ref "R9") (pin "2") (pinfunction "2_2") (pintype "passive"))
      (node (ref "S1") (pin "3") (pinfunction "3_3") (pintype "passive"))
      (node (ref "S1") (pin "4") (pinfunction "4_4") (pintype "passive"))
      (node (ref "S2") (pin "3") (pinfunction "3_3") (pintype "passive"))
      (node (ref "S2") (pin "4") (pinfunction "4_4") (pintype "passive"))
      (node (ref "S3") (pin "3") (pinfunction "3_3") (pintype "passive"))
      (node (ref "S3") (pin "4") (pinfunction "4_4") (pintype "passive"))
      (node (ref "S4") (pin "3") (pinfunction "3_3") (pintype "passive"))
      (node (ref "S4") (pin "4") (pinfunction "4_4") (pintype "passive"))
      (node (ref "S5") (pin "3") (pinfunction "3_3") (pintype "passive"))
      (node (ref "S5") (pin "4") (pinfunction "4_4") (pintype "passive"))
      (node (ref "T1") (pin "2") (pinfunction "S_2") (pintype "passive"))
      (node (ref "T2") (pin "2") (pinfunction "S_2") (pintype "passive"))
      (node (ref "T3") (pin "2") (pinfunction "S_2") (pintype "passive"))
      (node (ref "T4") (pin "2") (pinfunction "S_2") (pintype "passive"))
      (node (ref "U$1") (pin "1") (pinfunction "VSSOSC_1") (pintype "bidirectional"))
      (node (ref "U$1") (pin "13") (pinfunction "VSSPLL_13") (pintype "bidirectional"))
      (node (ref "U$1") (pin "14") (pinfunction "VSSRX_14") (pintype "bidirectional"))
      (node (ref "U$1") (pin "19") (pinfunction "VSSTX1_19") (pintype "bidirectional"))
      (node (ref "U$1") (pin "22") (pinfunction "VSSTX2_22") (pintype "bidirectional"))
      (node (ref "U$1") (pin "33") (pinfunction "VSS1_33") (pintype "bidirectional"))
      (node (ref "U$1") (pin "42") (pinfunction "VSS2_42") (pintype "bidirectional"))
      (node (ref "U$18") (pin "1") (pinfunction "GND_1") (pintype "bidirectional"))
      (node (ref "U$2") (pin "P$2") (pinfunction "P$2_P$2") (pintype "bidirectional"))
      (node (ref "U$3") (pin "1") (pinfunction "VSSOSC_1") (pintype "bidirectional"))
      (node (ref "U$3") (pin "13") (pinfunction "VSSPLL_13") (pintype "bidirectional"))
      (node (ref "U$3") (pin "14") (pinfunction "VSSRX_14") (pintype "bidirectional"))
      (node (ref "U$3") (pin "19") (pinfunction "VSSTX1_19") (pintype "bidirectional"))
      (node (ref "U$3") (pin "22") (pinfunction "VSSTX2_22") (pintype "bidirectional"))
      (node (ref "U$3") (pin "33") (pinfunction "VSS1_33") (pintype "bidirectional"))
      (node (ref "U$3") (pin "42") (pinfunction "VSS2_42") (pintype "bidirectional"))
      (node (ref "U$4") (pin "P$4") (pinfunction "GND_P$4") (pintype "bidirectional"))
      (node (ref "U$5") (pin "16") (pinfunction "VSS_16") (pintype "bidirectional"))
      (node (ref "U$5") (pin "32") (pinfunction "VSS_32") (pintype "bidirectional"))
      (node (ref "U2") (pin "23") (pinfunction "VSS_1_23") (pintype "bidirectional"))
      (node (ref "U2") (pin "35") (pinfunction "VSS_2_35") (pintype "passive"))
      (node (ref "U2") (pin "47") (pinfunction "VSS_3_47") (pintype "passive"))
      (node (ref "U2") (pin "8") (pinfunction "VSSA_8") (pintype "passive"))
      (node (ref "U3") (pin "4") (pinfunction "GND_4") (pintype "bidirectional"))
      (node (ref "U4") (pin "15") (pinfunction "GND_15") (pintype "passive"))
      (node (ref "U5") (pin "4") (pinfunction "GND_4") (pintype "passive"))
      (node (ref "U6") (pin "1") (pinfunction "VSS_1") (pintype "power_in"))
      (node (ref "U6") (pin "10") (pinfunction "DB3_10") (pintype "bidirectional"))
      (node (ref "U6") (pin "16") (pinfunction "K_16") (pintype "power_in"))
      (node (ref "U6") (pin "5") (pinfunction "R/W_5") (pintype "input"))
      (node (ref "U6") (pin "7") (pinfunction "DB0_7") (pintype "bidirectional"))
      (node (ref "U6") (pin "8") (pinfunction "DB1_8") (pintype "bidirectional"))
      (node (ref "U6") (pin "9") (pinfunction "DB2_9") (pintype "bidirectional"))
      (node (ref "X1") (pin "5") (pinfunction "5_5") (pintype "passive"))
    )
    (net (code "23") (name "G_RESET") (class "Default")
      (node (ref "C10") (pin "1") (pinfunction "1_1") (pintype "passive"))
      (node (ref "R4") (pin "1") (pinfunction "1_1") (pintype "passive"))
      (node (ref "S5") (pin "1") (pinfunction "1_1") (pintype "passive"))
      (node (ref "S5") (pin "2") (pinfunction "2_2") (pintype "passive"))
      (node (ref "U$5") (pin "4") (pinfunction "NRST_4") (pintype "bidirectional"))
      (node (ref "U2") (pin "7") (pinfunction "NRST_7") (pintype "bidirectional"))
    )
    (net (code "24") (name "I2C1_SCL") (class "Default")
      (node (ref "IC5") (pin "6") (pinfunction "SCL_6") (pintype "input"))
      (node (ref "JP4") (pin "2") (pinfunction "2_2") (pintype "passive"))
      (node (ref "R29") (pin "2") (pinfunction "2_2") (pintype "passive"))
      (node (ref "U2") (pin "42") (pinfunction "PB6_42") (pintype "bidirectional"))
    )
    (net (code "25") (name "I2C1_SDA") (class "Default")
      (node (ref "IC5") (pin "1") (pinfunction "SDA_1") (pintype "bidirectional"))
      (node (ref "JP4") (pin "3") (pinfunction "3_3") (pintype "passive"))
      (node (ref "R28") (pin "2") (pinfunction "2_2") (pintype "passive"))
      (node (ref "U2") (pin "43") (pinfunction "PB7_43") (pintype "bidirectional"))
    )
    (net (code "26") (name "LA1") (class "Default")
      (node (ref "J2") (pin "9") (pinfunction "G+_9") (pintype "bidirectional"))
      (node (ref "R17") (pin "1") (pinfunction "1_1") (pintype "passive"))
    )
    (net (code "27") (name "LA2") (class "Default")
      (node (ref "J3") (pin "9") (pinfunction "G+_9") (pintype "bidirectional"))
      (node (ref "R26") (pin "1") (pinfunction "1_1") (pintype "passive"))
    )
    (net (code "28") (name "LB1") (class "Default")
      (node (ref "J2") (pin "11") (pinfunction "Y+_11") (pintype "bidirectional"))
      (node (ref "R18") (pin "1") (pinfunction "1_1") (pintype "passive"))
    )
    (net (code "29") (name "LB2") (class "Default")
      (node (ref "J3") (pin "11") (pinfunction "Y+_11") (pintype "bidirectional"))
      (node (ref "R27") (pin "1") (pinfunction "1_1") (pintype "passive"))
    )
    (net (code "30") (name "LCD_D4") (class "Default")
      (node (ref "U$5") (pin "27") (pinfunction "PB4_27") (pintype "bidirectional"))
      (node (ref "U6") (pin "11") (pinfunction "DB4_11") (pintype "bidirectional"))
    )
    (net (code "31") (name "LCD_D5") (class "Default")
      (node (ref "U$5") (pin "28") (pinfunction "PB5_28") (pintype "bidirectional"))
      (node (ref "U6") (pin "12") (pinfunction "DB5_12") (pintype "bidirectional"))
    )
    (net (code "32") (name "LCD_D6") (class "Default")
      (node (ref "U$5") (pin "29") (pinfunction "PB6_29") (pintype "bidirectional"))
      (node (ref "U6") (pin "13") (pinfunction "DB6_13") (pintype "bidirectional"))
    )
    (net (code "33") (name "LCD_D7") (class "Default")
      (node (ref "U$5") (pin "30") (pinfunction "PB7_30") (pintype "bidirectional"))
      (node (ref "U6") (pin "14") (pinfunction "DB7_14") (pintype "bidirectional"))
    )
    (net (code "34") (name "LCD_E") (class "Default")
      (node (ref "U$5") (pin "26") (pinfunction "PB3_26") (pintype "bidirectional"))
      (node (ref "U6") (pin "6") (pinfunction "E_6") (pintype "input"))
    )
    (net (code "35") (name "LCD_RS") (class "Default")
      (node (ref "U$5") (pin "25") (pinfunction "PA15_25") (pintype "bidirectional"))
      (node (ref "U6") (pin "4") (pinfunction "RS_4") (pintype "input"))
    )
    (net (code "36") (name "Net-(BAT1-+)") (class "Default")
      (node (ref "BAT1") (pin "1") (pinfunction "+_1") (pintype "power_in"))
      (node (ref "D5") (pin "2") (pinfunction "A2_2") (pintype "passive"))
    )
    (net (code "37") (name "Net-(C26-+)") (class "Default")
      (node (ref "C26") (pin "A") (pinfunction "+_A") (pintype "passive"))
      (node (ref "U$1") (pin "43") (pinfunction "VCAP_43") (pintype "bidirectional"))
    )
    (net (code "38") (name "Net-(C40-+)") (class "Default")
      (node (ref "C40") (pin "A") (pinfunction "+_A") (pintype "passive"))
      (node (ref "U$3") (pin "43") (pinfunction "VCAP_43") (pintype "bidirectional"))
    )
    (net (code "39") (name "Net-(D8-PadA)") (class "Default")
      (node (ref "D8") (pin "A") (pinfunction "A_A") (pintype "passive"))
      (node (ref "F1") (pin "2") (pinfunction "2_2") (pintype "bidirectional"))
      (node (ref "R1") (pin "1") (pinfunction "1_1") (pintype "passive"))
    )
    (net (code "40") (name "Net-(F1-Pad1)") (class "Default")
      (node (ref "F1") (pin "1") (pinfunction "1_1") (pintype "bidirectional"))
      (node (ref "U$2") (pin "P$1") (pinfunction "P$1_P$1") (pintype "bidirectional"))
    )
    (net (code "41") (name "Net-(IC1-IN)") (class "Default")
      (node (ref "IC1") (pin "3") (pinfunction "IN_3") (pintype "input"))
      (node (ref "R2") (pin "1") (pinfunction "1_1") (pintype "passive"))
      (node (ref "R3") (pin "2") (pinfunction "2_2") (pintype "passive"))
      (node (ref "U$18") (pin "4") (pinfunction "VFB_4") (pintype "bidirectional"))
    )
    (net (code "42") (name "Net-(JP3-PadD+)") (class "Default")
      (node (ref "JP3") (pin "D+") (pinfunction "D+_D+") (pintype "bidirectional"))
      (node (ref "R6") (pin "2") (pinfunction "2_2") (pintype "passive"))
    )
    (net (code "43") (name "Net-(JP3-PadD-)") (class "Default")
      (node (ref "JP3") (pin "D-") (pinfunction "D-_D-") (pintype "bidirectional"))
      (node (ref "R5") (pin "2") (pinfunction "2_2") (pintype "passive"))
    )
    (net (code "44") (name "Net-(K1-PadO)") (class "Default")
      (node (ref "K1") (pin "O") (pinfunction "O_O") (pintype "passive"))
      (node (ref "U$14") (pin "P$1") (pinfunction "P$1_P$1") (pintype "bidirectional"))
    )
    (net (code "45") (name "Net-(K1-PadP)") (class "Default")
      (node (ref "K1") (pin "P") (pinfunction "P_P") (pintype "passive"))
      (node (ref "U$14") (pin "P$2") (pinfunction "P$2_P$2") (pintype "bidirectional"))
    )
    (net (code "46") (name "Net-(K1-PadS)") (class "Default")
      (node (ref "K1") (pin "S") (pinfunction "S_S") (pintype "passive"))
      (node (ref "U$14") (pin "P$3") (pinfunction "P$3_P$3") (pintype "bidirectional"))
    )
    (net (code "47") (name "Net-(K2-PadO)") (class "Default")
      (node (ref "K2") (pin "O") (pinfunction "O_O") (pintype "passive"))
      (node (ref "U$15") (pin "P$1") (pinfunction "P$1_P$1") (pintype "bidirectional"))
    )
    (net (code "48") (name "Net-(K2-PadP)") (class "Default")
      (node (ref "K2") (pin "P") (pinfunction "P_P") (pintype "passive"))
      (node (ref "U$15") (pin "P$2") (pinfunction "P$2_P$2") (pintype "bidirectional"))
    )
    (net (code "49") (name "Net-(K2-PadS)") (class "Default")
      (node (ref "K2") (pin "S") (pinfunction "S_S") (pintype "passive"))
      (node (ref "U$15") (pin "P$3") (pinfunction "P$3_P$3") (pintype "bidirectional"))
    )
    (net (code "50") (name "Net-(K3-PadO)") (class "Default")
      (node (ref "K3") (pin "O") (pinfunction "O_O") (pintype "passive"))
      (node (ref "U$16") (pin "P$1") (pinfunction "P$1_P$1") (pintype "bidirectional"))
    )
    (net (code "51") (name "Net-(K3-PadP)") (class "Default")
      (node (ref "K3") (pin "P") (pinfunction "P_P") (pintype "passive"))
      (node (ref "U$16") (pin "P$2") (pinfunction "P$2_P$2") (pintype "bidirectional"))
    )
    (net (code "52") (name "Net-(K3-PadS)") (class "Default")
      (node (ref "K3") (pin "S") (pinfunction "S_S") (pintype "passive"))
      (node (ref "U$16") (pin "P$3") (pinfunction "P$3_P$3") (pintype "bidirectional"))
    )
    (net (code "53") (name "Net-(K4-PadO)") (class "Default")
      (node (ref "K4") (pin "O") (pinfunction "O_O") (pintype "passive"))
      (node (ref "U$17") (pin "P$1") (pinfunction "P$1_P$1") (pintype "bidirectional"))
    )
    (net (code "54") (name "Net-(K4-PadP)") (class "Default")
      (node (ref "K4") (pin "P") (pinfunction "P_P") (pintype "passive"))
      (node (ref "U$17") (pin "P$2") (pinfunction "P$2_P$2") (pintype "bidirectional"))
    )
    (net (code "55") (name "Net-(K4-PadS)") (class "Default")
      (node (ref "K4") (pin "S") (pinfunction "S_S") (pintype "passive"))
      (node (ref "U$17") (pin "P$3") (pinfunction "P$3_P$3") (pintype "bidirectional"))
    )
    (net (code "56") (name "Net-(L3-1)") (class "Default")
      (node (ref "D4") (pin "C") (pinfunction "C_C") (pintype "passive"))
      (node (ref "L3") (pin "P$1") (pinfunction "1_P$1") (pintype "passive"))
      (node (ref "U3") (pin "2") (pinfunction "SWE_2") (pintype "bidirectional"))
    )
    (net (code "57") (name "Net-(L4-Pad1)") (class "Default")
      (node (ref "L4") (pin "1") (pinfunction "1_1") (pintype "passive"))
      (node (ref "R12") (pin "2") (pinfunction "2_2") (pintype "passive"))
      (node (ref "R13") (pin "2") (pinfunction "2_2") (pintype "passive"))
      (node (ref "R16") (pin "2") (pinfunction "2_2") (pintype "passive"))
    )
    (net (code "58") (name "Net-(L5-Pad1)") (class "Default")
      (node (ref "L5") (pin "1") (pinfunction "1_1") (pintype "passive"))
      (node (ref "R21") (pin "2") (pinfunction "2_2") (pintype "passive"))
      (node (ref "R22") (pin "2") (pinfunction "2_2") (pintype "passive"))
      (node (ref "R25") (pin "2") (pinfunction "2_2") (pintype "passive"))
    )
    (net (code "59") (name "Net-(LED1-PadA)") (class "Default")
      (node (ref "LED1") (pin "A") (pinfunction "A_A") (pintype "passive"))
      (node (ref "R31") (pin "2") (pinfunction "2_2") (pintype "passive"))
    )
    (net (code "60") (name "Net-(LED2-PadA)") (class "Default")
      (node (ref "LED2") (pin "A") (pinfunction "A_A") (pintype "passive"))
      (node (ref "R33") (pin "2") (pinfunction "2_2") (pintype "passive"))
    )
    (net (code "61") (name "Net-(LED3-PadA)") (class "Default")
      (node (ref "LED3") (pin "A") (pinfunction "A_A") (pintype "passive"))
      (node (ref "R34") (pin "2") (pinfunction "2_2") (pintype "passive"))
    )
    (net (code "62") (name "Net-(LED4-PadA)") (class "Default")
      (node (ref "LED4") (pin "A") (pinfunction "A_A") (pintype "passive"))
      (node (ref "R35") (pin "2") (pinfunction "2_2") (pintype "passive"))
    )
    (net (code "63") (name "Net-(LED5-PadA)") (class "Default")
      (node (ref "LED5") (pin "A") (pinfunction "A_A") (pintype "passive"))
      (node (ref "R36") (pin "2") (pinfunction "2_2") (pintype "passive"))
    )
    (net (code "64") (name "Net-(LED6-PadA)") (class "Default")
      (node (ref "LED6") (pin "A") (pinfunction "A_A") (pintype "passive"))
      (node (ref "R38") (pin "2") (pinfunction "2_2") (pintype "passive"))
    )
    (net (code "65") (name "Net-(LED7-PadA)") (class "Default")
      (node (ref "LED7") (pin "A") (pinfunction "A_A") (pintype "passive"))
      (node (ref "R37") (pin "2") (pinfunction "2_2") (pintype "passive"))
    )
    (net (code "66") (name "Net-(LED8-PadA)") (class "Default")
      (node (ref "LED8") (pin "A") (pinfunction "A_A") (pintype "passive"))
      (node (ref "R32") (pin "2") (pinfunction "2_2") (pintype "passive"))
    )
    (net (code "67") (name "Net-(LED9-PadA)") (class "Default")
      (node (ref "LED9") (pin "A") (pinfunction "A_A") (pintype "passive"))
      (node (ref "R39") (pin "2") (pinfunction "2_2") (pintype "passive"))
    )
    (net (code "68") (name "Net-(LED10-PadA)") (class "Default")
      (node (ref "LED10") (pin "A") (pinfunction "A_A") (pintype "passive"))
      (node (ref "R40") (pin "2") (pinfunction "2_2") (pintype "passive"))
    )
    (net (code "69") (name "Net-(LED11-PadA)") (class "Default")
      (node (ref "LED11") (pin "A") (pinfunction "A_A") (pintype "passive"))
      (node (ref "R41") (pin "2") (pinfunction "2_2") (pintype "passive"))
    )
    (net (code "70") (name "Net-(LED12-PadA)") (class "Default")
      (node (ref "LED12") (pin "A") (pinfunction "A_A") (pintype "passive"))
      (node (ref "R42") (pin "2") (pinfunction "2_2") (pintype "passive"))
    )
    (net (code "71") (name "Net-(LED13-PadA)") (class "Default")
      (node (ref "LED13") (pin "A") (pinfunction "A_A") (pintype "passive"))
      (node (ref "R44") (pin "2") (pinfunction "2_2") (pintype "passive"))
    )
    (net (code "72") (name "Net-(R30-WIPER)") (class "Default")
      (node (ref "R30") (pin "2") (pinfunction "WIPER_2") (pintype "passive"))
      (node (ref "U6") (pin "3") (pinfunction "VO_3") (pintype "bidirectional"))
    )
    (net (code "73") (name "Net-(T1-D)") (class "Default")
      (node (ref "D7") (pin "A") (pinfunction "A_A") (pintype "passive"))
      (node (ref "K1") (pin "2") (pinfunction "2_2") (pintype "passive"))
      (node (ref "T1") (pin "3") (pinfunction "D_3") (pintype "passive"))
    )
    (net (code "74") (name "Net-(T2-D)") (class "Default")
      (node (ref "D6") (pin "A") (pinfunction "A_A") (pintype "passive"))
      (node (ref "K2") (pin "2") (pinfunction "2_2") (pintype "passive"))
      (node (ref "T2") (pin "3") (pinfunction "D_3") (pintype "passive"))
    )
    (net (code "75") (name "Net-(T3-D)") (class "Default")
      (node (ref "D2") (pin "A") (pinfunction "A_A") (pintype "passive"))
      (node (ref "K3") (pin "2") (pinfunction "2_2") (pintype "passive"))
      (node (ref "T3") (pin "3") (pinfunction "D_3") (pintype "passive"))
    )
    (net (code "76") (name "Net-(T4-D)") (class "Default")
      (node (ref "D3") (pin "A") (pinfunction "A_A") (pintype "passive"))
      (node (ref "K4") (pin "2") (pinfunction "2_2") (pintype "passive"))
      (node (ref "T4") (pin "3") (pinfunction "D_3") (pintype "passive"))
    )
    (net (code "77") (name "Net-(U$1-LEDA)") (class "Default")
      (node (ref "R17") (pin "2") (pinfunction "2_2") (pintype "passive"))
      (node (ref "U$1") (pin "10") (pinfunction "LEDA_10") (pintype "bidirectional"))
    )
    (net (code "78") (name "Net-(U$1-LEDB)") (class "Default")
      (node (ref "R18") (pin "2") (pinfunction "2_2") (pintype "passive"))
      (node (ref "U$1") (pin "9") (pinfunction "LEDB_9") (pintype "bidirectional"))
    )
    (net (code "79") (name "Net-(U$1-OSC1)") (class "Default")
      (node (ref "C24") (pin "1") (pinfunction "1_1") (pintype "passive"))
      (node (ref "U$1") (pin "3") (pinfunction "OSC1_3") (pintype "bidirectional"))
      (node (ref "Y3") (pin "P$1") (pinfunction "1_P$1") (pintype "passive"))
    )
    (net (code "80") (name "Net-(U$1-OSC2)") (class "Default")
      (node (ref "C25") (pin "1") (pinfunction "1_1") (pintype "passive"))
      (node (ref "U$1") (pin "2") (pinfunction "OSC2_2") (pintype "bidirectional"))
      (node (ref "Y3") (pin "P$2") (pinfunction "2_P$2") (pintype "passive"))
    )
    (net (code "81") (name "Net-(U$1-RBIAS)") (class "Default")
      (node (ref "R10") (pin "2") (pinfunction "2_2") (pintype "passive"))
      (node (ref "U$1") (pin "11") (pinfunction "RBIAS_11") (pintype "bidirectional"))
    )
    (net (code "82") (name "Net-(U$1-TPIN+)") (class "Default")
      (node (ref "C30") (pin "1") (pinfunction "1_1") (pintype "passive"))
      (node (ref "R15") (pin "2") (pinfunction "2_2") (pintype "passive"))
      (node (ref "U$1") (pin "16") (pinfunction "TPIN+_16") (pintype "bidirectional"))
    )
    (net (code "83") (name "Net-(U$1-TPIN-)") (class "Default")
      (node (ref "C31") (pin "1") (pinfunction "1_1") (pintype "passive"))
      (node (ref "R14") (pin "2") (pinfunction "2_2") (pintype "passive"))
      (node (ref "U$1") (pin "17") (pinfunction "TPIN-_17") (pintype "bidirectional"))
    )
    (net (code "84") (name "Net-(U$1-~{INT{slash}SPISEL})") (class "Default")
      (node (ref "R11") (pin "1") (pinfunction "1_1") (pintype "passive"))
      (node (ref "U$1") (pin "24") (pinfunction "~{INT/SPISEL}_24") (pintype "bidirectional"))
    )
    (net (code "85") (name "Net-(U$3-LEDA)") (class "Default")
      (node (ref "R26") (pin "2") (pinfunction "2_2") (pintype "passive"))
      (node (ref "U$3") (pin "10") (pinfunction "LEDA_10") (pintype "bidirectional"))
    )
    (net (code "86") (name "Net-(U$3-LEDB)") (class "Default")
      (node (ref "R27") (pin "2") (pinfunction "2_2") (pintype "passive"))
      (node (ref "U$3") (pin "9") (pinfunction "LEDB_9") (pintype "bidirectional"))
    )
    (net (code "87") (name "Net-(U$3-OSC1)") (class "Default")
      (node (ref "C36") (pin "1") (pinfunction "1_1") (pintype "passive"))
      (node (ref "U$3") (pin "3") (pinfunction "OSC1_3") (pintype "bidirectional"))
      (node (ref "Y4") (pin "P$1") (pinfunction "1_P$1") (pintype "passive"))
    )
    (net (code "88") (name "Net-(U$3-OSC2)") (class "Default")
      (node (ref "C37") (pin "1") (pinfunction "1_1") (pintype "passive"))
      (node (ref "U$3") (pin "2") (pinfunction "OSC2_2") (pintype "bidirectional"))
      (node (ref "Y4") (pin "P$2") (pinfunction "2_P$2") (pintype "passive"))
    )
    (net (code "89") (name "Net-(U$3-RBIAS)") (class "Default")
      (node (ref "R19") (pin "2") (pinfunction "2_2") (pintype "passive"))
      (node (ref "U$3") (pin "11") (pinfunction "RBIAS_11") (pintype "bidirectional"))
    )
    (net (code "90") (name "Net-(U$3-TPIN+)") (class "Default")
      (node (ref "C42") (pin "1") (pinfunction "1_1") (pintype "passive"))
      (node (ref "R24") (pin "2") (pinfunction "2_2") (pintype "passive"))
      (node (ref "U$3") (pin "16") (pinfunction "TPIN+_16") (pintype "bidirectional"))
    )
    (net (code "91") (name "Net-(U$3-TPIN-)") (class "Default")
      (node (ref "C43") (pin "1") (pinfunction "1_1") (pintype "passive"))
      (node (ref "R23") (pin "2") (pinfunction "2_2") (pintype "passive"))
      (node (ref "U$3") (pin "17") (pinfunction "TPIN-_17") (pintype "bidirectional"))
    )
    (net (code "92") (name "Net-(U$3-~{INT{slash}SPISEL})") (class "Default")
      (node (ref "R20") (pin "1") (pinfunction "1_1") (pintype "passive"))
      (node (ref "U$3") (pin "24") (pinfunction "~{INT/SPISEL}_24") (pintype "bidirectional"))
    )
    (net (code "93") (name "Net-(U$4-S)") (class "Default")
      (node (ref "JP12") (pin "8") (pinfunction "8_8") (pintype "passive"))
      (node (ref "R43") (pin "1") (pinfunction "1_1") (pintype "passive"))
      (node (ref "U$4") (pin "P$2") (pinfunction "S_P$2") (pintype "bidirectional"))
    )
    (net (code "94") (name "Net-(U$5-BOOT0)") (class "Default")
      (node (ref "R48") (pin "1") (pinfunction "1_1") (pintype "passive"))
      (node (ref "U$5") (pin "31") (pinfunction "BOOT0_31") (pintype "bidirectional"))
    )
    (net (code "95") (name "Net-(U$5-PA13{slash}SWDIO)") (class "Default")
      (node (ref "JP11") (pin "3") (pinfunction "3_3") (pintype "passive"))
      (node (ref "U$5") (pin "23") (pinfunction "PA13/SWDIO_23") (pintype "bidirectional"))
    )
    (net (code "96") (name "Net-(U$5-PA14{slash}SWCLK)") (class "Default")
      (node (ref "JP11") (pin "2") (pinfunction "2_2") (pintype "passive"))
      (node (ref "U$5") (pin "24") (pinfunction "PA14/SWCLK_24") (pintype "bidirectional"))
    )
    (net (code "97") (name "Net-(U$18-SW)") (class "Default")
      (node (ref "C3") (pin "1") (pinfunction "1_1") (pintype "passive"))
      (node (ref "L1") (pin "2") (pinfunction "2_2") (pintype "passive"))
      (node (ref "U$18") (pin "2") (pinfunction "SW_2") (pintype "bidirectional"))
    )
    (net (code "98") (name "Net-(U$18-VBST)") (class "Default")
      (node (ref "C3") (pin "2") (pinfunction "2_2") (pintype "passive"))
      (node (ref "U$18") (pin "6") (pinfunction "VBST_6") (pintype "bidirectional"))
    )
    (net (code "99") (name "Net-(U2-BOOT0)") (class "Default")
      (node (ref "R47") (pin "2") (pinfunction "2_2") (pintype "passive"))
      (node (ref "U2") (pin "44") (pinfunction "BOOT0_44") (pintype "bidirectional"))
    )
    (net (code "100") (name "Net-(U2-PC14-OSC32_IN)") (class "Default")
      (node (ref "C12") (pin "1") (pinfunction "1_1") (pintype "passive"))
      (node (ref "U2") (pin "3") (pinfunction "PC14-OSC32_IN_3") (pintype "bidirectional"))
      (node (ref "Y1") (pin "1") (pinfunction "1_1") (pintype "passive"))
    )
    (net (code "101") (name "Net-(U2-PC15-OSC32_OUT)") (class "Default")
      (node (ref "C11") (pin "1") (pinfunction "1_1") (pintype "passive"))
      (node (ref "U2") (pin "4") (pinfunction "PC15-OSC32_OUT_4") (pintype "bidirectional"))
      (node (ref "Y1") (pin "4") (pinfunction "2_4") (pintype "passive"))
    )
    (net (code "102") (name "Net-(U2-PD0-OSC_IN)") (class "Default")
      (node (ref "C13") (pin "1") (pinfunction "1_1") (pintype "passive"))
      (node (ref "R46") (pin "2") (pinfunction "2_2") (pintype "passive"))
      (node (ref "U2") (pin "5") (pinfunction "PD0-OSC_IN_5") (pintype "bidirectional"))
      (node (ref "Y2") (pin "2") (pinfunction "2_2") (pintype "passive"))
    )
    (net (code "103") (name "Net-(U2-PD1-OSC_OUT)") (class "Default")
      (node (ref "C14") (pin "1") (pinfunction "1_1") (pintype "passive"))
      (node (ref "R46") (pin "1") (pinfunction "1_1") (pintype "passive"))
      (node (ref "U2") (pin "6") (pinfunction "PD1-OSC_OUT_6") (pintype "bidirectional"))
      (node (ref "Y2") (pin "1") (pinfunction "1_1") (pintype "passive"))
    )
    (net (code "104") (name "Net-(U3-COMP)") (class "Default")
      (node (ref "R8") (pin "1") (pinfunction "1_1") (pintype "passive"))
      (node (ref "R9") (pin "1") (pinfunction "1_1") (pintype "passive"))
      (node (ref "U3") (pin "5") (pinfunction "COMP_5") (pintype "bidirectional"))
    )
    (net (code "105") (name "Net-(U3-TC)") (class "Default")
      (node (ref "C17") (pin "1") (pinfunction "1_1") (pintype "passive"))
      (node (ref "U3") (pin "3") (pinfunction "TC_3") (pintype "bidirectional"))
    )
    (net (code "106") (name "Net-(U4-C1+)") (class "Default")
      (node (ref "C18") (pin "1") (pinfunction "1_1") (pintype "passive"))
      (node (ref "U4") (pin "1") (pinfunction "C1+_1") (pintype "input"))
    )
    (net (code "107") (name "Net-(U4-C1-)") (class "Default")
      (node (ref "C18") (pin "2") (pinfunction "2_2") (pintype "passive"))
      (node (ref "U4") (pin "3") (pinfunction "C1-_3") (pintype "input"))
    )
    (net (code "108") (name "Net-(U4-C2+)") (class "Default")
      (node (ref "C19") (pin "2") (pinfunction "2_2") (pintype "passive"))
      (node (ref "U4") (pin "4") (pinfunction "C2+_4") (pintype "input"))
    )
    (net (code "109") (name "Net-(U4-C2-)") (class "Default")
      (node (ref "C19") (pin "1") (pinfunction "1_1") (pintype "passive"))
      (node (ref "U4") (pin "5") (pinfunction "C2-_5") (pintype "input"))
    )
    (net (code "110") (name "Net-(U4-V+)") (class "Default")
      (node (ref "C21") (pin "2") (pinfunction "2_2") (pintype "passive"))
      (node (ref "U4") (pin "2") (pinfunction "V+_2") (pintype "input"))
    )
    (net (code "111") (name "Net-(U4-V-)") (class "Default")
      (node (ref "C20") (pin "2") (pinfunction "2_2") (pintype "passive"))
      (node (ref "U4") (pin "6") (pinfunction "V-_6") (pintype "input"))
    )
    (net (code "112") (name "RX1+") (class "Default")
      (node (ref "C30") (pin "2") (pinfunction "2_2") (pintype "passive"))
      (node (ref "J2") (pin "4") (pinfunction "RD+_4") (pintype "bidirectional"))
    )
    (net (code "113") (name "RX1-") (class "Default")
      (node (ref "C31") (pin "2") (pinfunction "2_2") (pintype "passive"))
      (node (ref "J2") (pin "6") (pinfunction "RD-_6") (pintype "bidirectional"))
    )
    (net (code "114") (name "RX1_CT") (class "Default")
      (node (ref "C32") (pin "2") (pinfunction "2_2") (pintype "passive"))
      (node (ref "J2") (pin "5") (pinfunction "RXCT_5") (pintype "bidirectional"))
      (node (ref "R14") (pin "1") (pinfunction "1_1") (pintype "passive"))
      (node (ref "R15") (pin "1") (pinfunction "1_1") (pintype "passive"))
    )
    (net (code "115") (name "RX2+") (class "Default")
      (node (ref "C42") (pin "2") (pinfunction "2_2") (pintype "passive"))
      (node (ref "J3") (pin "4") (pinfunction "RD+_4") (pintype "bidirectional"))
    )
    (net (code "116") (name "RX2-") (class "Default")
      (node (ref "C43") (pin "2") (pinfunction "2_2") (pintype "passive"))
      (node (ref "J3") (pin "6") (pinfunction "RD-_6") (pintype "bidirectional"))
    )
    (net (code "117") (name "RX2_CT") (class "Default")
      (node (ref "C44") (pin "2") (pinfunction "2_2") (pintype "passive"))
      (node (ref "J3") (pin "5") (pinfunction "RXCT_5") (pintype "bidirectional"))
      (node (ref "R23") (pin "1") (pinfunction "1_1") (pintype "passive"))
      (node (ref "R24") (pin "1") (pinfunction "1_1") (pintype "passive"))
    )
    (net (code "118") (name "SPI1_MISO") (class "Default")
      (node (ref "JP1") (pin "2") (pinfunction "2_2") (pintype "passive"))
      (node (ref "U$1") (pin "35") (pinfunction "SO/WR/EN_35") (pintype "bidirectional"))
      (node (ref "U2") (pin "16") (pinfunction "PA6_16") (pintype "bidirectional"))
    )
    (net (code "119") (name "SPI1_MOSI") (class "Default")
      (node (ref "JP1") (pin "3") (pinfunction "3_3") (pintype "passive"))
      (node (ref "U$1") (pin "36") (pinfunction "SI/RD/~{RW}_36") (pintype "bidirectional"))
      (node (ref "U2") (pin "17") (pinfunction "PA7_17") (pintype "bidirectional"))
    )
    (net (code "120") (name "SPI1_SCK") (class "Default")
      (node (ref "JP1") (pin "4") (pinfunction "4_4") (pintype "passive"))
      (node (ref "U$1") (pin "37") (pinfunction "SCK/AL_37") (pintype "bidirectional"))
      (node (ref "U2") (pin "15") (pinfunction "PA5_15") (pintype "bidirectional"))
    )
    (net (code "121") (name "SPI1_SS1_ETH1") (class "Default")
      (node (ref "JP1") (pin "1") (pinfunction "1_1") (pintype "passive"))
      (node (ref "U$1") (pin "34") (pinfunction "CS/~{CS}_34") (pintype "bidirectional"))
      (node (ref "U2") (pin "18") (pinfunction "PB0_18") (pintype "bidirectional"))
    )
    (net (code "122") (name "SPI2_MISO") (class "Default")
      (node (ref "JP5") (pin "6") (pinfunction "6_6") (pintype "passive"))
      (node (ref "U$3") (pin "35") (pinfunction "SO/WR/EN_35") (pintype "bidirectional"))
      (node (ref "U2") (pin "27") (pinfunction "PB14_27") (pintype "bidirectional"))
      (node (ref "U5") (pin "2") (pinfunction "SO_(IO1)_2") (pintype "output"))
    )
    (net (code "123") (name "SPI2_MOSI") (class "Default")
      (node (ref "JP5") (pin "5") (pinfunction "5_5") (pintype "passive"))
      (node (ref "U$3") (pin "36") (pinfunction "SI/RD/~{RW}_36") (pintype "bidirectional"))
      (node (ref "U2") (pin "28") (pinfunction "PB15_28") (pintype "bidirectional"))
      (node (ref "U5") (pin "5") (pinfunction "SI_(IO0)_5") (pintype "bidirectional"))
    )
    (net (code "124") (name "SPI2_SCK") (class "Default")
      (node (ref "JP5") (pin "7") (pinfunction "7_7") (pintype "passive"))
      (node (ref "U$3") (pin "37") (pinfunction "SCK/AL_37") (pintype "bidirectional"))
      (node (ref "U2") (pin "26") (pinfunction "PB13_26") (pintype "bidirectional"))
      (node (ref "U5") (pin "6") (pinfunction "CLK_6") (pintype "input"))
    )
    (net (code "125") (name "SPI2_SS1_ETH2") (class "Default")
      (node (ref "JP5") (pin "3") (pinfunction "3_3") (pintype "passive"))
      (node (ref "U$3") (pin "34") (pinfunction "CS/~{CS}_34") (pintype "bidirectional"))
      (node (ref "U2") (pin "29") (pinfunction "PA8_29") (pintype "bidirectional"))
    )
    (net (code "126") (name "SPI2_SS2_FLASH") (class "Default")
      (node (ref "JP5") (pin "4") (pinfunction "4_4") (pintype "passive"))
      (node (ref "U2") (pin "25") (pinfunction "PB12_25") (pintype "bidirectional"))
      (node (ref "U5") (pin "1") (pinfunction "CS_1") (pintype "input"))
    )
    (net (code "127") (name "SW0") (class "Default")
      (node (ref "S1") (pin "1") (pinfunction "1_1") (pintype "passive"))
      (node (ref "S1") (pin "2") (pinfunction "2_2") (pintype "passive"))
      (node (ref "U$5") (pin "2") (pinfunction "PF0/OSC_IN_2") (pintype "bidirectional"))
    )
    (net (code "128") (name "SW1") (class "Default")
      (node (ref "S2") (pin "1") (pinfunction "1_1") (pintype "passive"))
      (node (ref "S2") (pin "2") (pinfunction "2_2") (pintype "passive"))
      (node (ref "U$5") (pin "3") (pinfunction "PF1/OSC_OUT_3") (pintype "bidirectional"))
    )
    (net (code "129") (name "SW2") (class "Default")
      (node (ref "S3") (pin "1") (pinfunction "1_1") (pintype "passive"))
      (node (ref "S3") (pin "2") (pinfunction "2_2") (pintype "passive"))
      (node (ref "U2") (pin "14") (pinfunction "PA4_14") (pintype "bidirectional"))
    )
    (net (code "130") (name "SW3") (class "Default")
      (node (ref "S4") (pin "1") (pinfunction "1_1") (pintype "passive"))
      (node (ref "S4") (pin "2") (pinfunction "2_2") (pintype "passive"))
      (node (ref "U2") (pin "19") (pinfunction "PB1_19") (pintype "bidirectional"))
    )
    (net (code "131") (name "SWDCLK") (class "Default")
      (node (ref "JP2") (pin "2") (pinfunction "2_2") (pintype "passive"))
      (node (ref "U2") (pin "37") (pinfunction "PA14_37") (pintype "bidirectional"))
    )
    (net (code "132") (name "SWDIO") (class "Default")
      (node (ref "JP2") (pin "3") (pinfunction "3_3") (pintype "passive"))
      (node (ref "U2") (pin "34") (pinfunction "PA13_34") (pintype "bidirectional"))
    )
    (net (code "133") (name "TX1+") (class "Default")
      (node (ref "J2") (pin "1") (pinfunction "TD+_1") (pintype "bidirectional"))
      (node (ref "R12") (pin "1") (pinfunction "1_1") (pintype "passive"))
      (node (ref "U$1") (pin "20") (pinfunction "TPOUT+_20") (pintype "bidirectional"))
    )
    (net (code "134") (name "TX1-") (class "Default")
      (node (ref "J2") (pin "3") (pinfunction "TD-_3") (pintype "bidirectional"))
      (node (ref "R13") (pin "1") (pinfunction "1_1") (pintype "passive"))
      (node (ref "U$1") (pin "21") (pinfunction "TPOUT-_21") (pintype "bidirectional"))
    )
    (net (code "135") (name "TX1_CT") (class "Default")
      (node (ref "C29") (pin "1") (pinfunction "1_1") (pintype "passive"))
      (node (ref "J2") (pin "2") (pinfunction "TXCT_2") (pintype "bidirectional"))
      (node (ref "R16") (pin "1") (pinfunction "1_1") (pintype "passive"))
    )
    (net (code "136") (name "TX2+") (class "Default")
      (node (ref "J3") (pin "1") (pinfunction "TD+_1") (pintype "bidirectional"))
      (node (ref "R21") (pin "1") (pinfunction "1_1") (pintype "passive"))
      (node (ref "U$3") (pin "20") (pinfunction "TPOUT+_20") (pintype "bidirectional"))
    )
    (net (code "137") (name "TX2-") (class "Default")
      (node (ref "J3") (pin "3") (pinfunction "TD-_3") (pintype "bidirectional"))
      (node (ref "R22") (pin "1") (pinfunction "1_1") (pintype "passive"))
      (node (ref "U$3") (pin "21") (pinfunction "TPOUT-_21") (pintype "bidirectional"))
    )
    (net (code "138") (name "TX2_CT") (class "Default")
      (node (ref "C41") (pin "1") (pinfunction "1_1") (pintype "passive"))
      (node (ref "J3") (pin "2") (pinfunction "TXCT_2") (pintype "bidirectional"))
      (node (ref "R25") (pin "1") (pinfunction "1_1") (pintype "passive"))
    )
    (net (code "139") (name "UART_RX1") (class "Default")
      (node (ref "JP6") (pin "1") (pinfunction "1_1") (pintype "passive"))
      (node (ref "U2") (pin "22") (pinfunction "PB11_22") (pintype "bidirectional"))
    )
    (net (code "140") (name "UART_RX2") (class "Default")
      (node (ref "JP7") (pin "2") (pinfunction "2_2") (pintype "passive"))
      (node (ref "U2") (pin "31") (pinfunction "PA10_31") (pintype "bidirectional"))
      (node (ref "U4") (pin "12") (pinfunction "R1OUT_12") (pintype "output"))
    )
    (net (code "141") (name "UART_TX1") (class "Default")
      (node (ref "JP6") (pin "2") (pinfunction "2_2") (pintype "passive"))
      (node (ref "U2") (pin "21") (pinfunction "PB10_21") (pintype "bidirectional"))
    )
    (net (code "142") (name "UART_TX2") (class "Default")
      (node (ref "JP7") (pin "3") (pinfunction "3_3") (pintype "passive"))
      (node (ref "U2") (pin "30") (pinfunction "PA9_30") (pintype "bidirectional"))
      (node (ref "U4") (pin "11") (pinfunction "T1IN_11") (pintype "input"))
    )
    (net (code "143") (name "USB_D+") (class "Default")
      (node (ref "R45") (pin "1") (pinfunction "1_1") (pintype "passive"))
      (node (ref "R6") (pin "1") (pinfunction "1_1") (pintype "passive"))
      (node (ref "U2") (pin "33") (pinfunction "PA12_33") (pintype "bidirectional"))
    )
    (net (code "144") (name "USB_D-") (class "Default")
      (node (ref "R5") (pin "1") (pinfunction "1_1") (pintype "passive"))
      (node (ref "U2") (pin "32") (pinfunction "PA11_32") (pintype "power_in"))
    )
    (net (code "145") (name "VBAT") (class "Default")
      (node (ref "D5") (pin "3") (pinfunction "C_3") (pintype "passive"))
      (node (ref "U2") (pin "1") (pinfunction "VBAT_1") (pintype "input"))
    )
    (net (code "146") (name "VIN") (class "Default")
      (node (ref "C15") (pin "+") (pinfunction "+_+") (pintype "passive"))
      (node (ref "D8") (pin "C") (pinfunction "C_C") (pintype "passive"))
      (node (ref "R7") (pin "2") (pinfunction "2_2") (pintype "passive"))
      (node (ref "U3") (pin "6") (pinfunction "VCC_6") (pintype "bidirectional"))
    )
    (net (code "147") (name "VIN2") (class "Default")
      (node (ref "R7") (pin "1") (pinfunction "1_1") (pintype "passive"))
      (node (ref "U3") (pin "1") (pinfunction "SWC_1") (pintype "bidirectional"))
      (node (ref "U3") (pin "7") (pinfunction "SEN_7") (pintype "bidirectional"))
      (node (ref "U3") (pin "8") (pinfunction "DVR_8") (pintype "bidirectional"))
    )
    (net (code "148") (name "unconnected-(IC5-DNC-Pad3)") (class "Default")
      (node (ref "IC5") (pin "3") (pinfunction "DNC_3") (pintype "no_connect"))
    )
    (net (code "149") (name "unconnected-(IC5-DNC-Pad4)") (class "Default")
      (node (ref "IC5") (pin "4") (pinfunction "DNC_4") (pintype "no_connect"))
    )
    (net (code "150") (name "unconnected-(J2-NC-Pad7)") (class "Default")
      (node (ref "J2") (pin "7") (pinfunction "NC_7") (pintype "bidirectional"))
    )
    (net (code "151") (name "unconnected-(J3-NC-Pad7)") (class "Default")
      (node (ref "J3") (pin "7") (pinfunction "NC_7") (pintype "bidirectional"))
    )
    (net (code "152") (name "unconnected-(JP3-PadVBUS)") (class "Default")
      (node (ref "JP3") (pin "VBUS") (pinfunction "VBUS_VBUS") (pintype "bidirectional"))
    )
    (net (code "153") (name "unconnected-(JP12-Pad4)") (class "Default")
      (node (ref "JP12") (pin "4") (pinfunction "4_4") (pintype "passive"))
    )
    (net (code "154") (name "unconnected-(JP12-Pad6)") (class "Default")
      (node (ref "JP12") (pin "6") (pinfunction "6_6") (pintype "passive"))
    )
    (net (code "155") (name "unconnected-(JP12-Pad9)") (class "Default")
      (node (ref "JP12") (pin "9") (pinfunction "9_9") (pintype "passive"))
    )
    (net (code "156") (name "unconnected-(JP12-Pad10)") (class "Default")
      (node (ref "JP12") (pin "10") (pinfunction "10_10") (pintype "passive"))
    )
    (net (code "157") (name "unconnected-(U$1-AD0-Pad38)") (class "Default")
      (node (ref "U$1") (pin "38") (pinfunction "AD0_38") (pintype "bidirectional"))
    )
    (net (code "158") (name "unconnected-(U$1-AD1-Pad39)") (class "Default")
      (node (ref "U$1") (pin "39") (pinfunction "AD1_39") (pintype "bidirectional"))
    )
    (net (code "159") (name "unconnected-(U$1-AD2-Pad40)") (class "Default")
      (node (ref "U$1") (pin "40") (pinfunction "AD2_40") (pintype "bidirectional"))
    )
    (net (code "160") (name "unconnected-(U$1-AD3-Pad41)") (class "Default")
      (node (ref "U$1") (pin "41") (pinfunction "AD3_41") (pintype "bidirectional"))
    )
    (net (code "161") (name "unconnected-(U$1-AD4-Pad5)") (class "Default")
      (node (ref "U$1") (pin "5") (pinfunction "AD4_5") (pintype "bidirectional"))
    )
    (net (code "162") (name "unconnected-(U$1-AD5-Pad6)") (class "Default")
      (node (ref "U$1") (pin "6") (pinfunction "AD5_6") (pintype "bidirectional"))
    )
    (net (code "163") (name "unconnected-(U$1-AD6-Pad7)") (class "Default")
      (node (ref "U$1") (pin "7") (pinfunction "AD6_7") (pintype "bidirectional"))
    )
    (net (code "164") (name "unconnected-(U$1-AD7-Pad8)") (class "Default")
      (node (ref "U$1") (pin "8") (pinfunction "AD7_8") (pintype "bidirectional"))
    )
    (net (code "165") (name "unconnected-(U$1-AD8-Pad25)") (class "Default")
      (node (ref "U$1") (pin "25") (pinfunction "AD8_25") (pintype "bidirectional"))
    )
    (net (code "166") (name "unconnected-(U$1-AD9-Pad26)") (class "Default")
      (node (ref "U$1") (pin "26") (pinfunction "AD9_26") (pintype "bidirectional"))
    )
    (net (code "167") (name "unconnected-(U$1-AD10-Pad27)") (class "Default")
      (node (ref "U$1") (pin "27") (pinfunction "AD10_27") (pintype "bidirectional"))
    )
    (net (code "168") (name "unconnected-(U$1-AD11-Pad28)") (class "Default")
      (node (ref "U$1") (pin "28") (pinfunction "AD11_28") (pintype "bidirectional"))
    )
    (net (code "169") (name "unconnected-(U$1-AD12-Pad29)") (class "Default")
      (node (ref "U$1") (pin "29") (pinfunction "AD12_29") (pintype "bidirectional"))
    )
    (net (code "170") (name "unconnected-(U$1-AD13-Pad30)") (class "Default")
      (node (ref "U$1") (pin "30") (pinfunction "AD13_30") (pintype "bidirectional"))
    )
    (net (code "171") (name "unconnected-(U$1-AD14-Pad31)") (class "Default")
      (node (ref "U$1") (pin "31") (pinfunction "AD14_31") (pintype "bidirectional"))
    )
    (net (code "172") (name "unconnected-(U$1-CLKOUT-Pad23)") (class "Default")
      (node (ref "U$1") (pin "23") (pinfunction "CLKOUT_23") (pintype "bidirectional"))
    )
    (net (code "173") (name "unconnected-(U$1-PSPCFG0-Pad32)") (class "Default")
      (node (ref "U$1") (pin "32") (pinfunction "PSPCFG0_32") (pintype "bidirectional"))
    )
    (net (code "174") (name "unconnected-(U$3-AD0-Pad38)") (class "Default")
      (node (ref "U$3") (pin "38") (pinfunction "AD0_38") (pintype "bidirectional"))
    )
    (net (code "175") (name "unconnected-(U$3-AD1-Pad39)") (class "Default")
      (node (ref "U$3") (pin "39") (pinfunction "AD1_39") (pintype "bidirectional"))
    )
    (net (code "176") (name "unconnected-(U$3-AD2-Pad40)") (class "Default")
      (node (ref "U$3") (pin "40") (pinfunction "AD2_40") (pintype "bidirectional"))
    )
    (net (code "177") (name "unconnected-(U$3-AD3-Pad41)") (class "Default")
      (node (ref "U$3") (pin "41") (pinfunction "AD3_41") (pintype "bidirectional"))
    )
    (net (code "178") (name "unconnected-(U$3-AD4-Pad5)") (class "Default")
      (node (ref "U$3") (pin "5") (pinfunction "AD4_5") (pintype "bidirectional"))
    )
    (net (code "179") (name "unconnected-(U$3-AD5-Pad6)") (class "Default")
      (node (ref "U$3") (pin "6") (pinfunction "AD5_6") (pintype "bidirectional"))
    )
    (net (code "180") (name "unconnected-(U$3-AD6-Pad7)") (class "Default")
      (node (ref "U$3") (pin "7") (pinfunction "AD6_7") (pintype "bidirectional"))
    )
    (net (code "181") (name "unconnected-(U$3-AD7-Pad8)") (class "Default")
      (node (ref "U$3") (pin "8") (pinfunction "AD7_8") (pintype "bidirectional"))
    )
    (net (code "182") (name "unconnected-(U$3-AD8-Pad25)") (class "Default")
      (node (ref "U$3") (pin "25") (pinfunction "AD8_25") (pintype "bidirectional"))
    )
    (net (code "183") (name "unconnected-(U$3-AD9-Pad26)") (class "Default")
      (node (ref "U$3") (pin "26") (pinfunction "AD9_26") (pintype "bidirectional"))
    )
    (net (code "184") (name "unconnected-(U$3-AD10-Pad27)") (class "Default")
      (node (ref "U$3") (pin "27") (pinfunction "AD10_27") (pintype "bidirectional"))
    )
    (net (code "185") (name "unconnected-(U$3-AD11-Pad28)") (class "Default")
      (node (ref "U$3") (pin "28") (pinfunction "AD11_28") (pintype "bidirectional"))
    )
    (net (code "186") (name "unconnected-(U$3-AD12-Pad29)") (class "Default")
      (node (ref "U$3") (pin "29") (pinfunction "AD12_29") (pintype "bidirectional"))
    )
    (net (code "187") (name "unconnected-(U$3-AD13-Pad30)") (class "Default")
      (node (ref "U$3") (pin "30") (pinfunction "AD13_30") (pintype "bidirectional"))
    )
    (net (code "188") (name "unconnected-(U$3-AD14-Pad31)") (class "Default")
      (node (ref "U$3") (pin "31") (pinfunction "AD14_31") (pintype "bidirectional"))
    )
    (net (code "189") (name "unconnected-(U$3-CLKOUT-Pad23)") (class "Default")
      (node (ref "U$3") (pin "23") (pinfunction "CLKOUT_23") (pintype "bidirectional"))
    )
    (net (code "190") (name "unconnected-(U$3-PSPCFG0-Pad32)") (class "Default")
      (node (ref "U$3") (pin "32") (pinfunction "PSPCFG0_32") (pintype "bidirectional"))
    )
    (net (code "191") (name "unconnected-(U$5-PA12-Pad22)") (class "Default")
      (node (ref "U$5") (pin "22") (pinfunction "PA12_22") (pintype "bidirectional"))
    )
    (net (code "192") (name "unconnected-(U2-PA0-WKUP-Pad10)") (class "Default")
      (node (ref "U2") (pin "10") (pinfunction "PA0-WKUP_10") (pintype "bidirectional"))
    )
    (net (code "193") (name "unconnected-(U2-PA1-Pad11)") (class "Default")
      (node (ref "U2") (pin "11") (pinfunction "PA1_11") (pintype "bidirectional"))
    )
    (net (code "194") (name "unconnected-(U2-PA15-Pad38)") (class "Default")
      (node (ref "U2") (pin "38") (pinfunction "PA15_38") (pintype "bidirectional"))
    )
    (net (code "195") (name "unconnected-(U2-PB2-Pad20)") (class "Default")
      (node (ref "U2") (pin "20") (pinfunction "PB2_20") (pintype "bidirectional"))
    )
    (net (code "196") (name "unconnected-(U2-PB3-Pad39)") (class "Default")
      (node (ref "U2") (pin "39") (pinfunction "PB3_39") (pintype "bidirectional"))
    )
    (net (code "197") (name "unconnected-(U2-PB4-Pad40)") (class "Default")
      (node (ref "U2") (pin "40") (pinfunction "PB4_40") (pintype "bidirectional"))
    )
    (net (code "198") (name "unconnected-(U2-PB5-Pad41)") (class "Default")
      (node (ref "U2") (pin "41") (pinfunction "PB5_41") (pintype "bidirectional"))
    )
    (net (code "199") (name "unconnected-(U2-PB8-Pad45)") (class "Default")
      (node (ref "U2") (pin "45") (pinfunction "PB8_45") (pintype "bidirectional"))
    )
    (net (code "200") (name "unconnected-(U2-PB9-Pad46)") (class "Default")
      (node (ref "U2") (pin "46") (pinfunction "PB9_46") (pintype "bidirectional"))
    )
    (net (code "201") (name "unconnected-(U2-PC13-TAMPER-RTC-Pad2)") (class "Default")
      (node (ref "U2") (pin "2") (pinfunction "PC13-TAMPER-RTC_2") (pintype "bidirectional"))
    )
    (net (code "202") (name "unconnected-(U4-R2IN-Pad8)") (class "Default")
      (node (ref "U4") (pin "8") (pinfunction "R2IN_8") (pintype "input"))
    )
    (net (code "203") (name "unconnected-(U4-R2OUT-Pad9)") (class "Default")
      (node (ref "U4") (pin "9") (pinfunction "R2OUT_9") (pintype "output"))
    )
    (net (code "204") (name "unconnected-(U4-T2IN-Pad10)") (class "Default")
      (node (ref "U4") (pin "10") (pinfunction "T2IN_10") (pintype "input"))
    )
    (net (code "205") (name "unconnected-(U4-T2OUT-Pad7)") (class "Default")
      (node (ref "U4") (pin "7") (pinfunction "T2OUT_7") (pintype "output"))
    )
    (net (code "206") (name "unconnected-(U5-HOLD_(IO3)-Pad7)") (class "Default")
      (node (ref "U5") (pin "7") (pinfunction "HOLD_(IO3)_7") (pintype "bidirectional"))
    )
    (net (code "207") (name "unconnected-(U5-WP_(IO2)-Pad3)") (class "Default")
      (node (ref "U5") (pin "3") (pinfunction "WP_(IO2)_3") (pintype "bidirectional"))
    )
    (net (code "208") (name "unconnected-(X1-Pad1)") (class "Default")
      (node (ref "X1") (pin "1") (pinfunction "1_1") (pintype "passive"))
    )
    (net (code "209") (name "unconnected-(X1-Pad4)") (class "Default")
      (node (ref "X1") (pin "4") (pinfunction "4_4") (pintype "passive"))
    )
    (net (code "210") (name "unconnected-(X1-Pad6)") (class "Default")
      (node (ref "X1") (pin "6") (pinfunction "6_6") (pintype "passive"))
    )
    (net (code "211") (name "unconnected-(X1-Pad7)") (class "Default")
      (node (ref "X1") (pin "7") (pinfunction "7_7") (pintype "passive"))
    )
    (net (code "212") (name "unconnected-(X1-Pad8)") (class "Default")
      (node (ref "X1") (pin "8") (pinfunction "8_8") (pintype "passive"))
    )
    (net (code "213") (name "unconnected-(X1-Pad9)") (class "Default")
      (node (ref "X1") (pin "9") (pinfunction "9_9") (pintype "passive"))
    )
  )
)
